# rev1.net
KiCad netlist of a schematic drawn in EAGLE
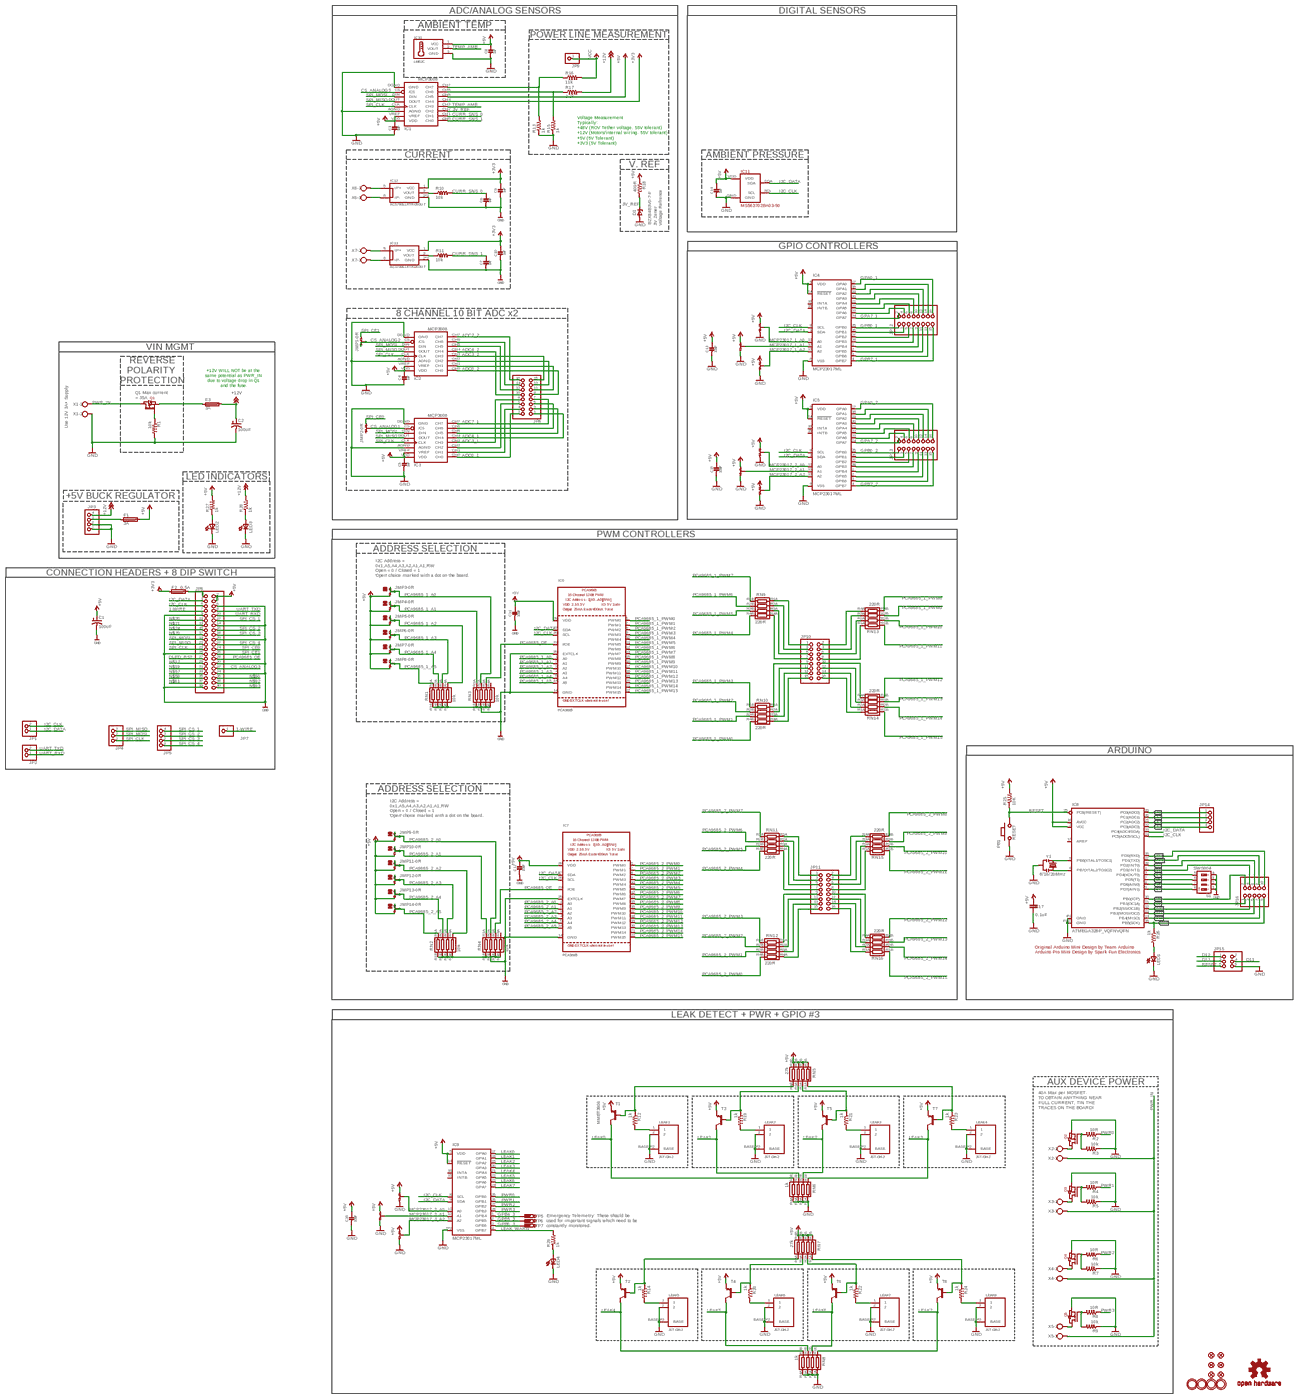
[diagram p0: schematic, sheet 1, overview]
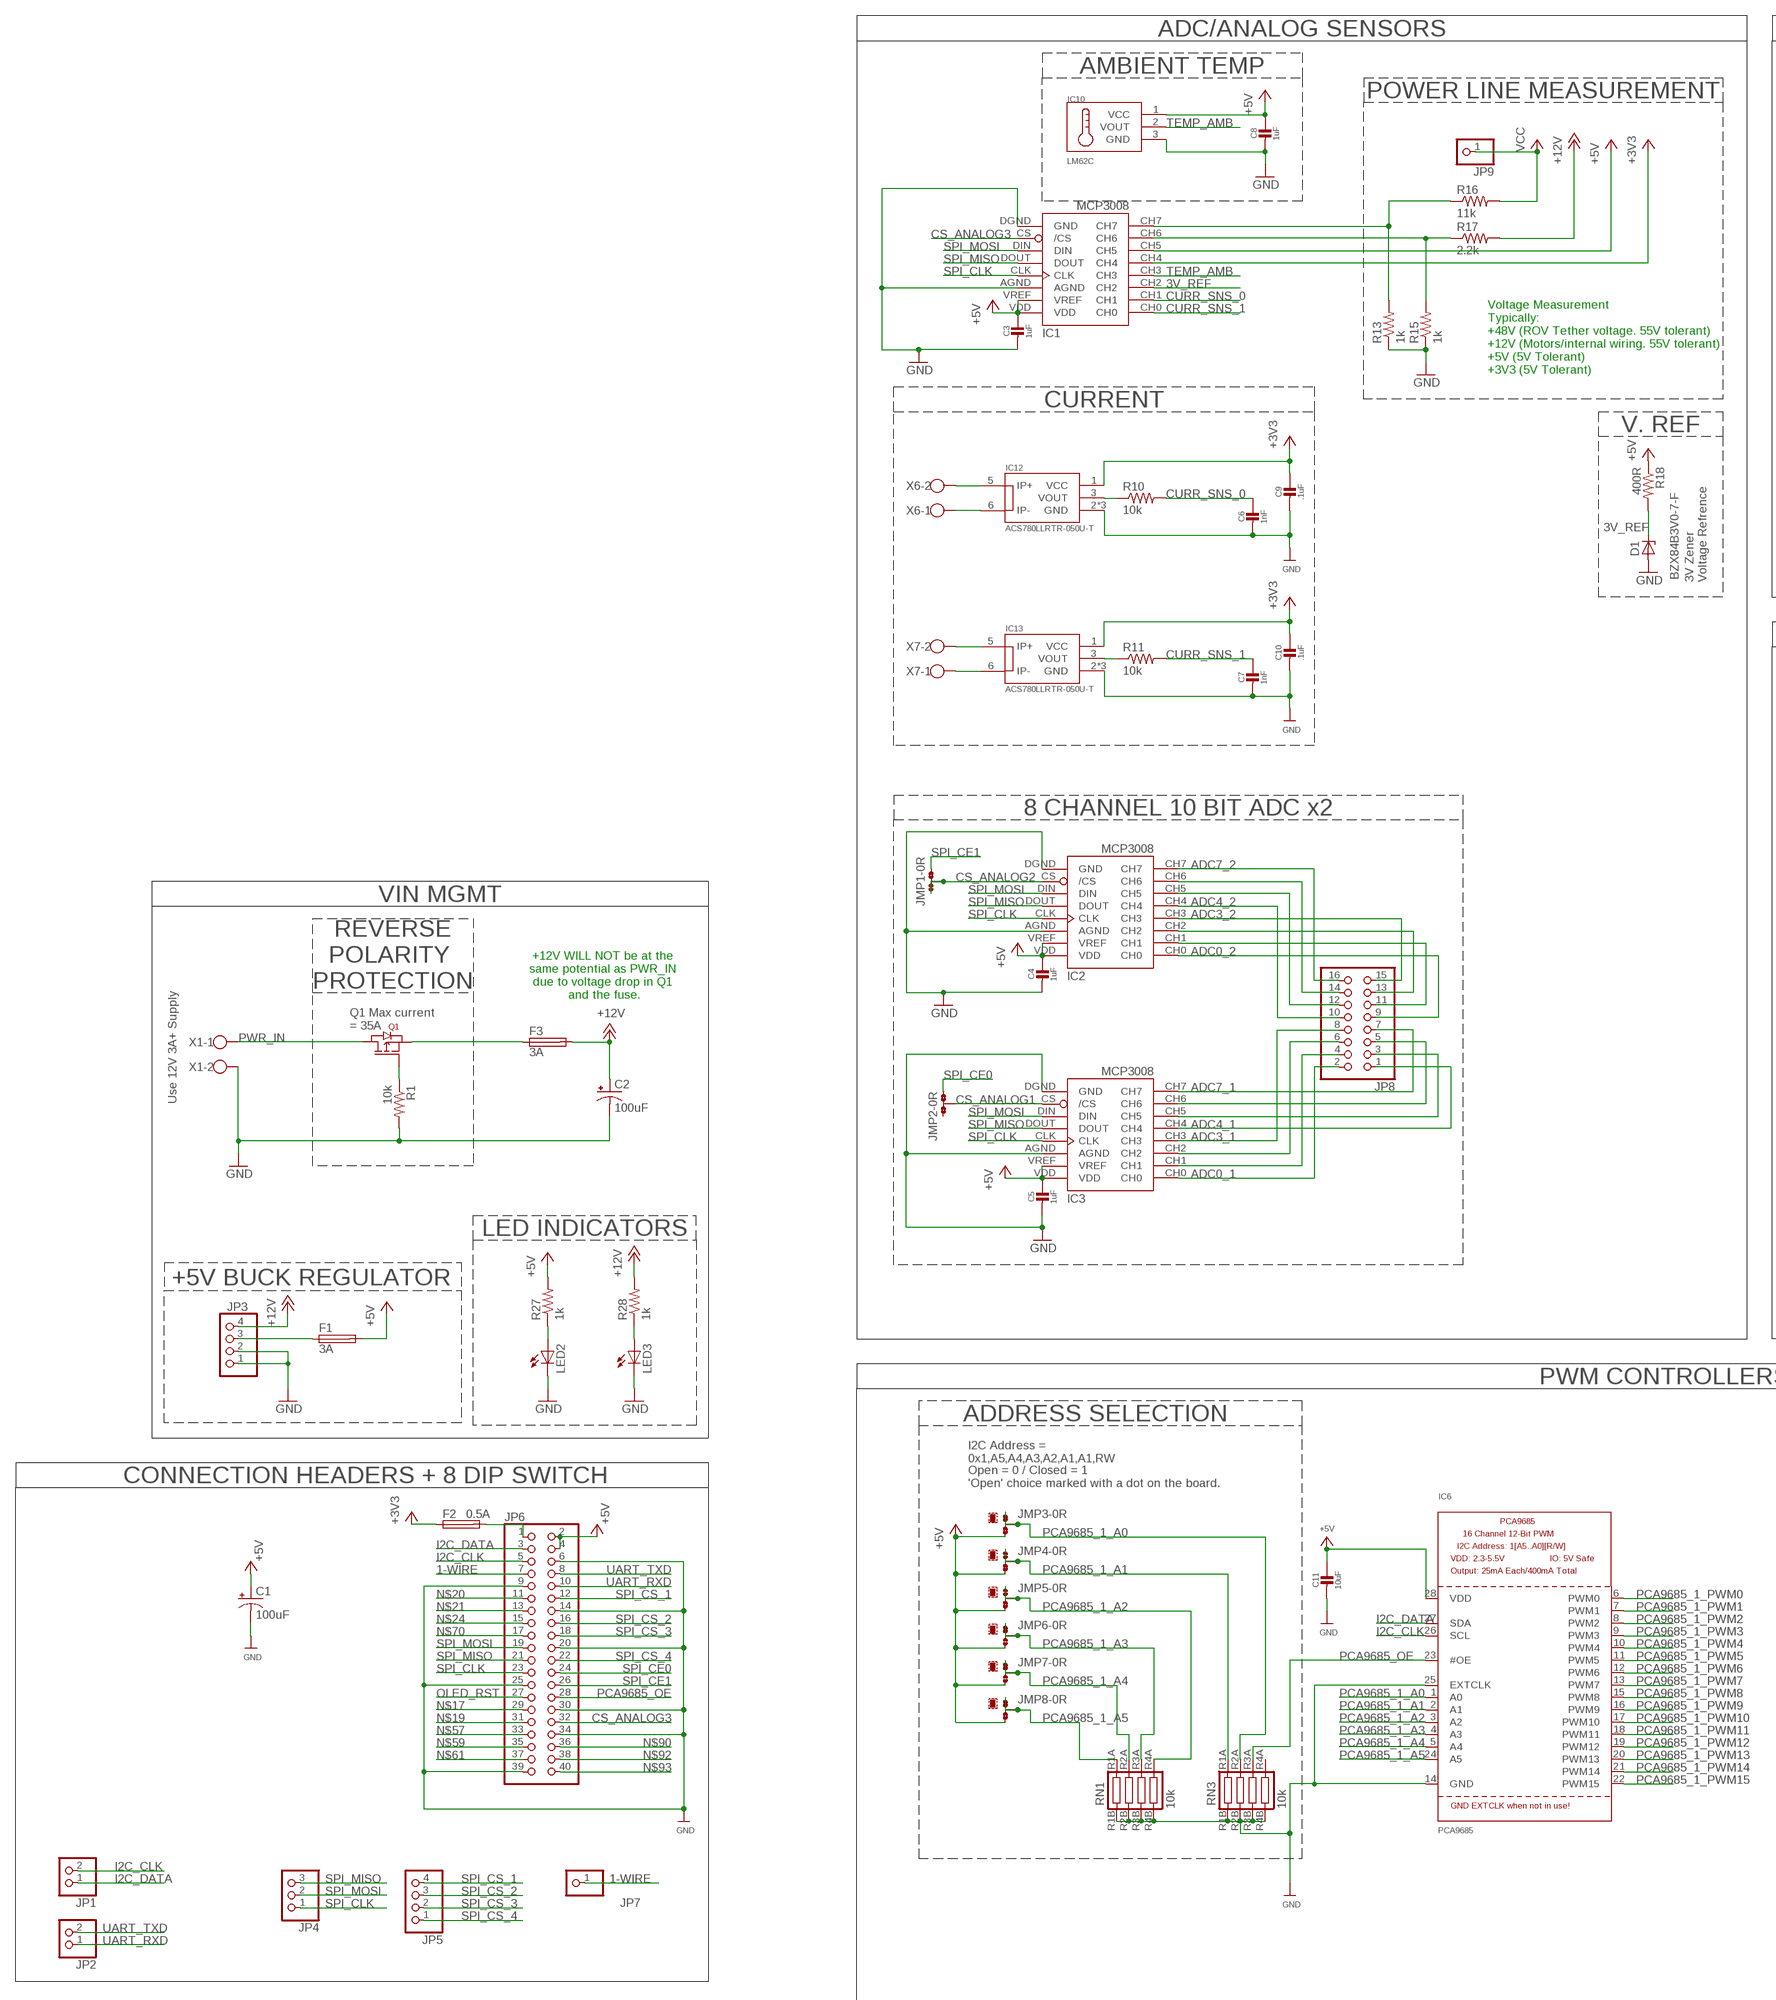
[diagram p1: schematic, sheet 1, part 1 of 4]
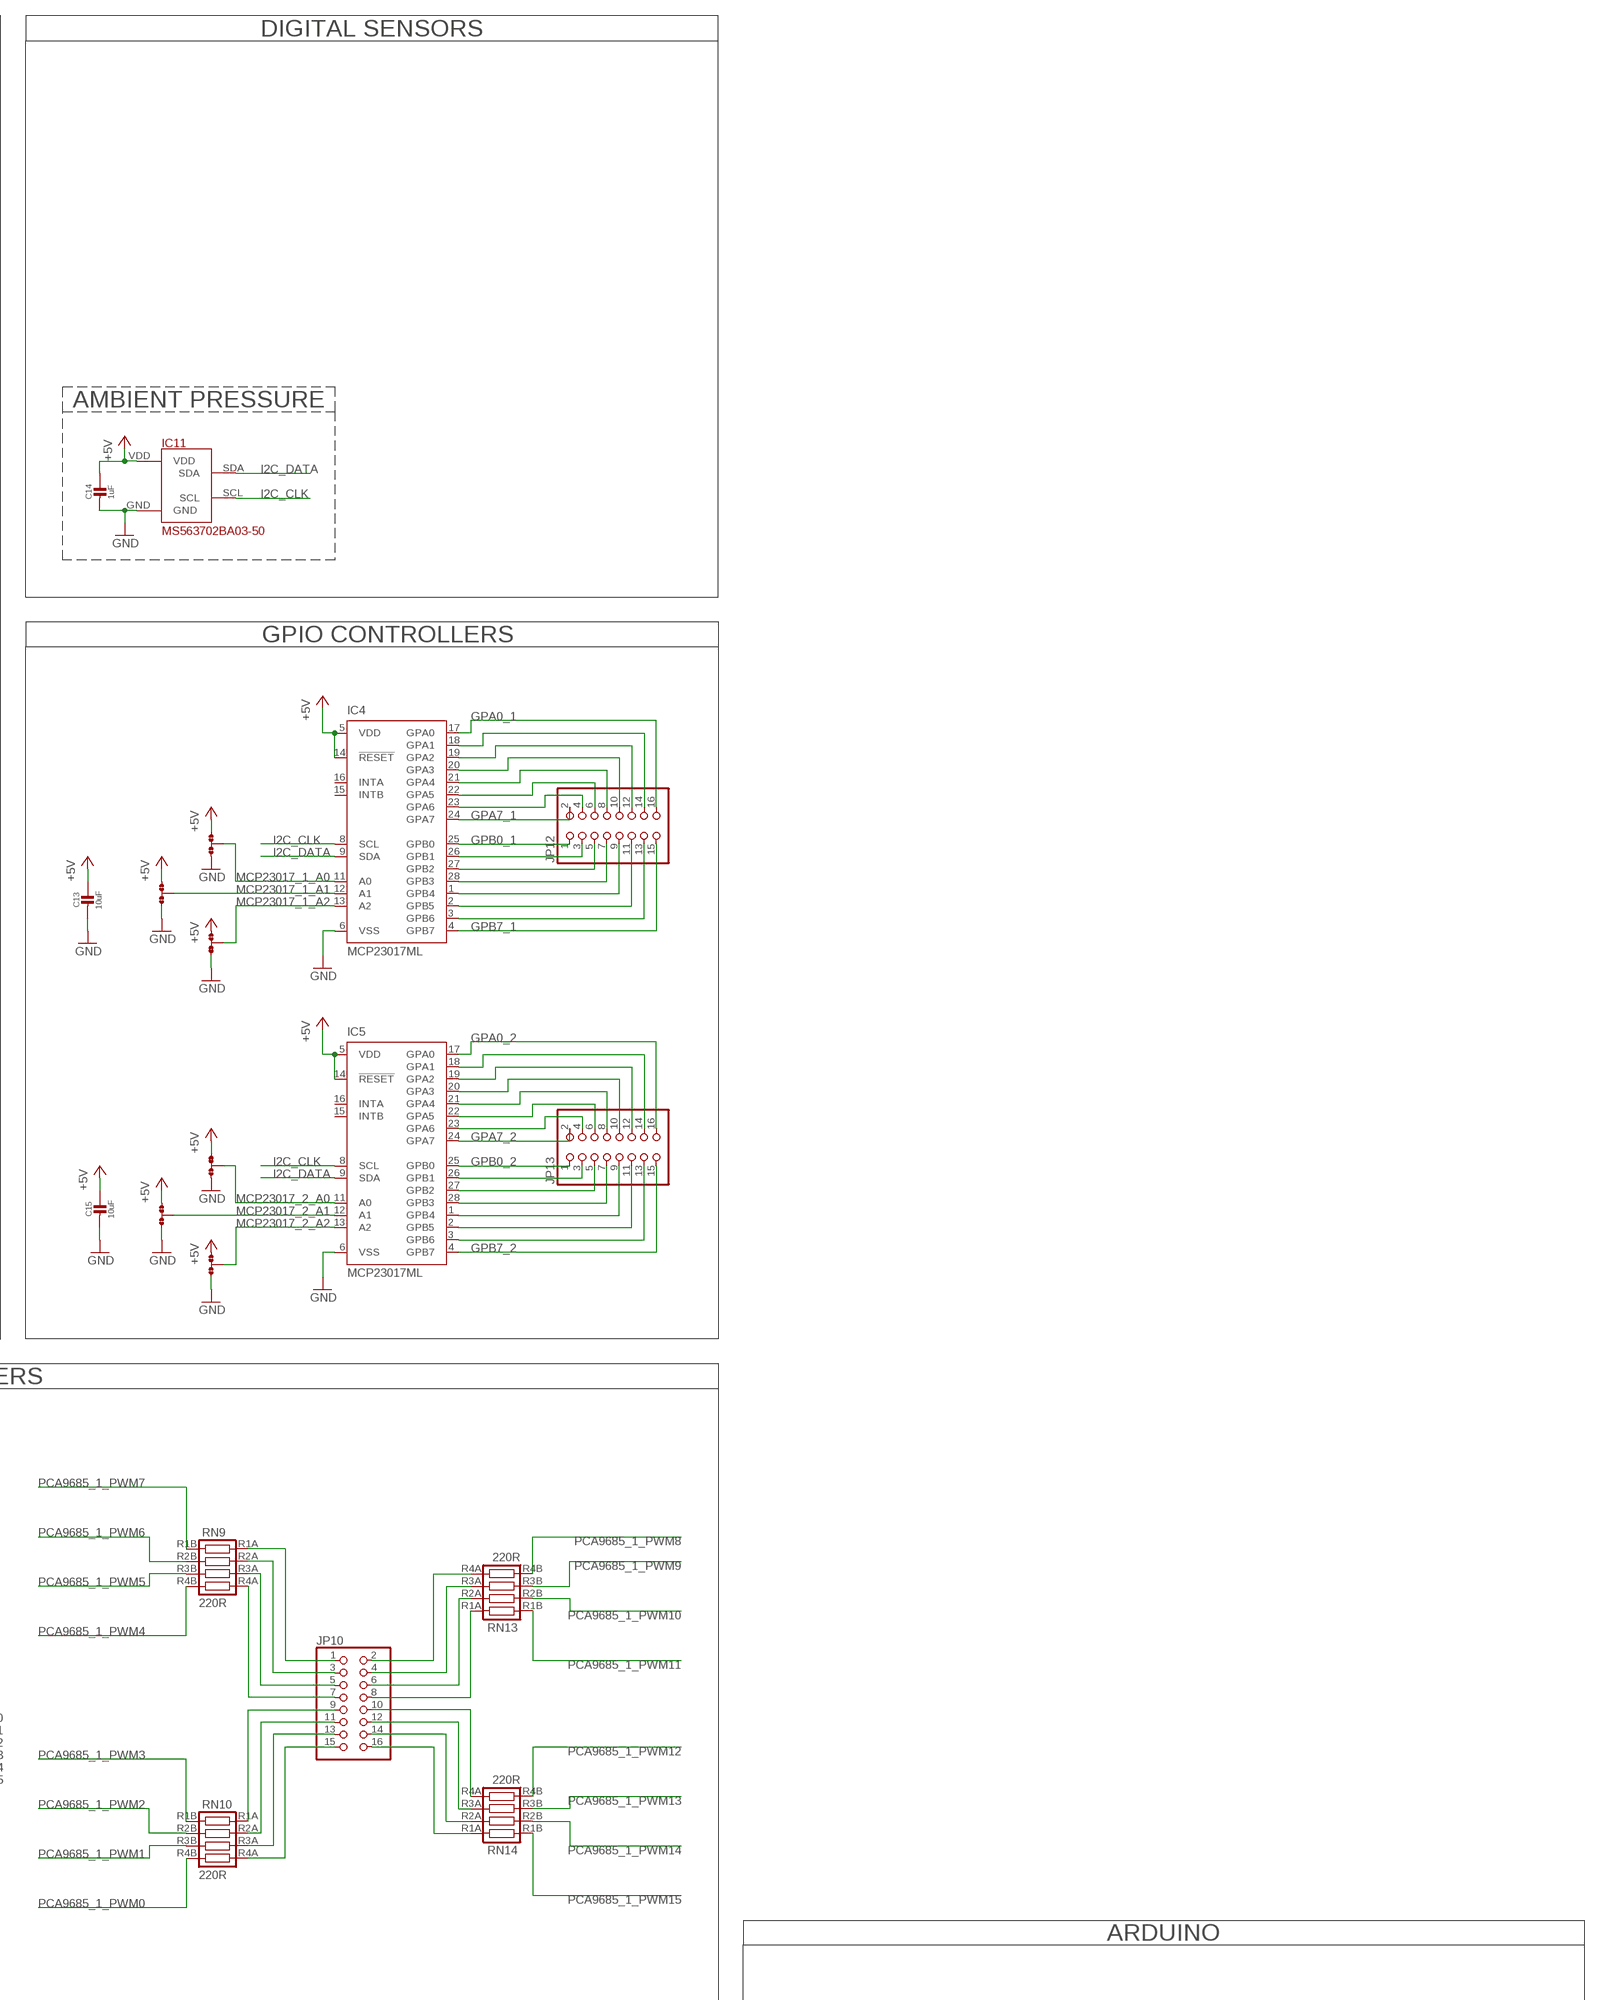
[diagram p2: schematic, sheet 1, part 2 of 4]
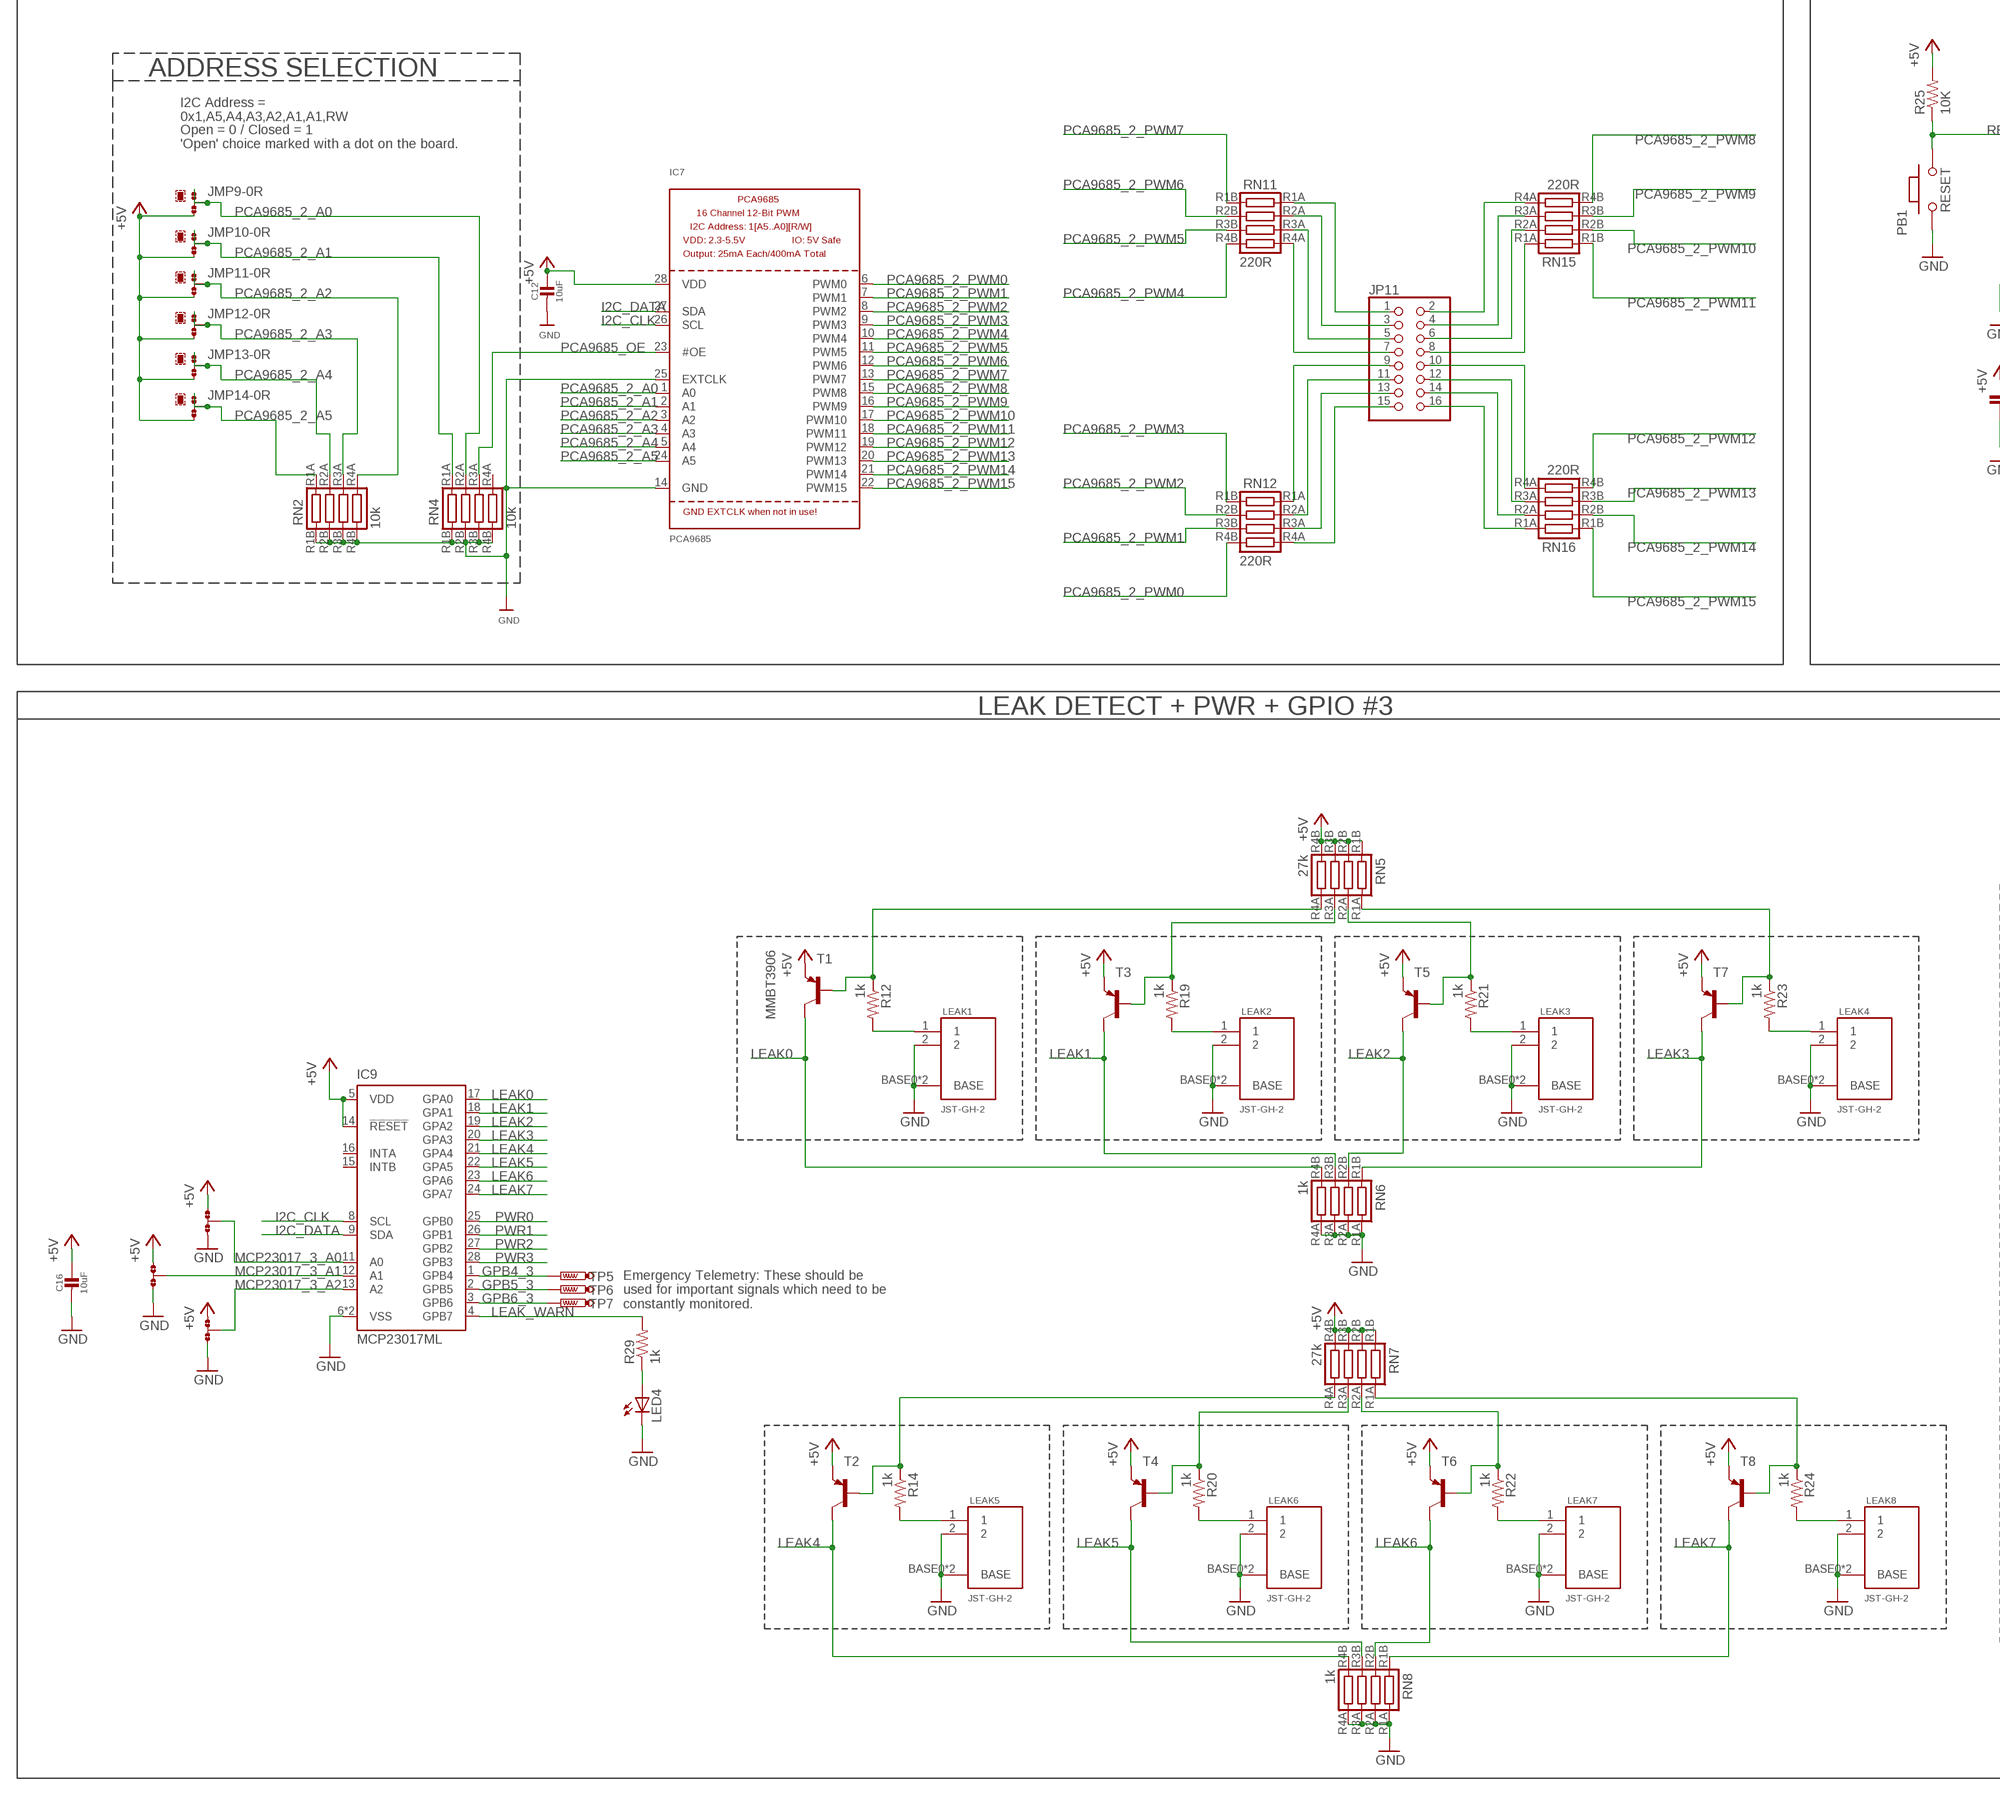
[diagram p3: schematic, sheet 1, part 3 of 4]
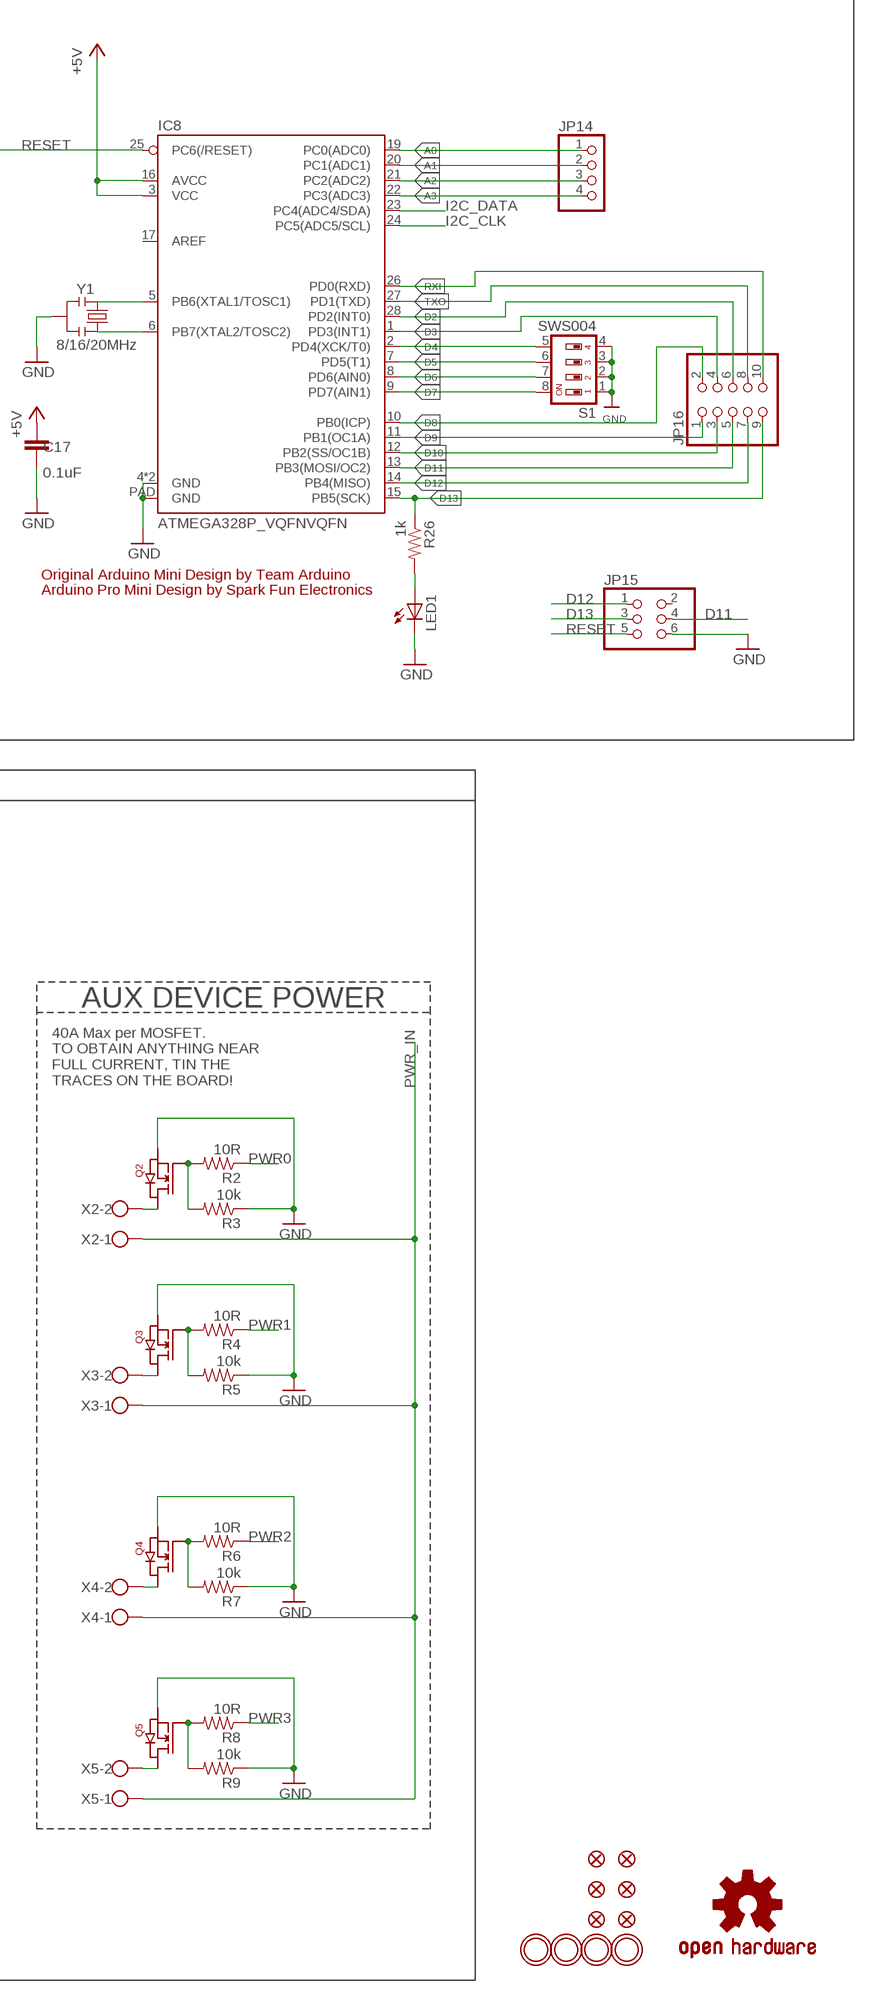
[diagram p4: schematic, sheet 1, part 4 of 4]

(export (version "E")
  (design (tool "Eeschema 10.0.6"))
  (components
    (comp (ref "1")
      (value "MOUNTINGHOLE2.5")
      (footprint "eagle-import:MOUNTINGHOLE_2.5_PLATED")
      (libsource (lib "eagle-import") (part "MOUNTINGHOLE2.5"))
    )
    (comp (ref "2")
      (value "MOUNTINGHOLE2.5")
      (footprint "eagle-import:MOUNTINGHOLE_2.5_PLATED")
      (libsource (lib "eagle-import") (part "MOUNTINGHOLE2.5"))
    )
    (comp (ref "3")
      (value "MOUNTINGHOLE2.5")
      (footprint "eagle-import:MOUNTINGHOLE_2.5_PLATED")
      (libsource (lib "eagle-import") (part "MOUNTINGHOLE2.5"))
    )
    (comp (ref "4")
      (value "MOUNTINGHOLE2.5")
      (footprint "eagle-import:MOUNTINGHOLE_2.5_PLATED")
      (libsource (lib "eagle-import") (part "MOUNTINGHOLE2.5"))
    )
    (comp (ref "5")
      (value "OSHW-LOGOS")
      (footprint "eagle-import:OSHW-LOGO-S")
      (libsource (lib "eagle-import") (part "OSHW-LOGOS"))
    )
    (comp (ref "C1")
      (value "100uF")
      (footprint "eagle-import:153CLV-0807")
      (libsource (lib "eagle-import") (part "CPOL-US153CLV-0807"))
    )
    (comp (ref "C2")
      (value "100uF")
      (footprint "eagle-import:153CLV-0807")
      (libsource (lib "eagle-import") (part "CPOL-US153CLV-0807"))
    )
    (comp (ref "C3")
      (value "1uF")
      (footprint "eagle-import:0805-NO")
      (libsource (lib "eagle-import") (part "CAP_CERAMIC0805-NOOUTLINE"))
    )
    (comp (ref "C4")
      (value "1uF")
      (footprint "eagle-import:0805-NO")
      (libsource (lib "eagle-import") (part "CAP_CERAMIC0805-NOOUTLINE"))
    )
    (comp (ref "C5")
      (value "1uF")
      (footprint "eagle-import:0805-NO")
      (libsource (lib "eagle-import") (part "CAP_CERAMIC0805-NOOUTLINE"))
    )
    (comp (ref "C6")
      (value "1nF")
      (footprint "eagle-import:0805-NO")
      (libsource (lib "eagle-import") (part "CAP_CERAMIC0805-NOOUTLINE"))
    )
    (comp (ref "C7")
      (value "1nF")
      (footprint "eagle-import:0805-NO")
      (libsource (lib "eagle-import") (part "CAP_CERAMIC0805-NOOUTLINE"))
    )
    (comp (ref "C8")
      (value "1uF")
      (footprint "eagle-import:0805-NO")
      (libsource (lib "eagle-import") (part "CAP_CERAMIC0805-NOOUTLINE"))
    )
    (comp (ref "C9")
      (value ".1uF")
      (footprint "eagle-import:0805-NO")
      (libsource (lib "eagle-import") (part "CAP_CERAMIC0805-NOOUTLINE"))
    )
    (comp (ref "C10")
      (value ".1uF")
      (footprint "eagle-import:0805-NO")
      (libsource (lib "eagle-import") (part "CAP_CERAMIC0805-NOOUTLINE"))
    )
    (comp (ref "C11")
      (value "10uF")
      (footprint "eagle-import:0805-NO")
      (libsource (lib "eagle-import") (part "CAP_CERAMIC0805-NOOUTLINE"))
    )
    (comp (ref "C12")
      (value "10uF")
      (footprint "eagle-import:0805-NO")
      (libsource (lib "eagle-import") (part "CAP_CERAMIC0805-NOOUTLINE"))
    )
    (comp (ref "C13")
      (value "10uF")
      (footprint "eagle-import:0805-NO")
      (libsource (lib "eagle-import") (part "CAP_CERAMIC0805-NOOUTLINE"))
    )
    (comp (ref "C14")
      (value "1uF")
      (footprint "eagle-import:0805-NO")
      (libsource (lib "eagle-import") (part "CAP_CERAMIC0805-NOOUTLINE"))
    )
    (comp (ref "C15")
      (value "10uF")
      (footprint "eagle-import:0805-NO")
      (libsource (lib "eagle-import") (part "CAP_CERAMIC0805-NOOUTLINE"))
    )
    (comp (ref "C16")
      (value "10uF")
      (footprint "eagle-import:0805-NO")
      (libsource (lib "eagle-import") (part "CAP_CERAMIC0805-NOOUTLINE"))
    )
    (comp (ref "C17")
      (value "0.1uF")
      (footprint "eagle-import:C0805")
      (libsource (lib "eagle-import") (part "C-EUC0805"))
    )
    (comp (ref "D1")
      (value "BZX84B3V0-7-F")
      (footprint "eagle-import:SOT23")
      (libsource (lib "eagle-import") (part "ZENER-DIODESOT23"))
    )
    (comp (ref "F1")
      (value "3A")
      (footprint "eagle-import:2920_(7351_METRIC)")
      (libsource (lib "eagle-import") (part "PTC_FUSE3"))
    )
    (comp (ref "F2")
      (value "0.5A")
      (footprint "eagle-import:1210_(3225METRIC)")
      (libsource (lib "eagle-import") (part "PTC_FUSE2"))
    )
    (comp (ref "F3")
      (value "3A")
      (footprint "eagle-import:2920_(7351_METRIC)")
      (libsource (lib "eagle-import") (part "PTC_FUSE3"))
    )
    (comp (ref "FID1")
      (value "FIDUCIAL\"\"")
      (footprint "eagle-import:FIDUCIAL_1MM")
      (libsource (lib "eagle-import") (part "FIDUCIAL{dblquote}{dblquote}"))
    )
    (comp (ref "FID2")
      (value "FIDUCIAL\"\"")
      (footprint "eagle-import:FIDUCIAL_1MM")
      (libsource (lib "eagle-import") (part "FIDUCIAL{dblquote}{dblquote}"))
    )
    (comp (ref "FID3")
      (value "FIDUCIAL\"\"")
      (footprint "eagle-import:FIDUCIAL_1MM")
      (libsource (lib "eagle-import") (part "FIDUCIAL{dblquote}{dblquote}"))
    )
    (comp (ref "FID4")
      (value "FIDUCIAL\"\"")
      (footprint "eagle-import:FIDUCIAL_1MM")
      (libsource (lib "eagle-import") (part "FIDUCIAL{dblquote}{dblquote}"))
    )
    (comp (ref "FID5")
      (value "FIDUCIAL\"\"")
      (footprint "eagle-import:FIDUCIAL_1MM")
      (libsource (lib "eagle-import") (part "FIDUCIAL{dblquote}{dblquote}"))
    )
    (comp (ref "FID6")
      (value "FIDUCIAL\"\"")
      (footprint "eagle-import:FIDUCIAL_1MM")
      (libsource (lib "eagle-import") (part "FIDUCIAL{dblquote}{dblquote}"))
    )
    (comp (ref "IC1")
      (value "U2")
      (footprint "eagle-import:MCP3008")
      (libsource (lib "eagle-import") (part "MCP3008"))
    )
    (comp (ref "IC2")
      (value "U2")
      (footprint "eagle-import:MCP3008")
      (libsource (lib "eagle-import") (part "MCP3008"))
    )
    (comp (ref "IC3")
      (value "U2")
      (footprint "eagle-import:MCP3008")
      (libsource (lib "eagle-import") (part "MCP3008"))
    )
    (comp (ref "IC4")
      (value "MCP23017ML")
      (footprint "eagle-import:QFN28-ML_6X6MM")
      (fields (field (name "MF") "MICROCHIP") (field (name "MPN") "MCP23017-E/ML"))
      (libsource (lib "eagle-import") (part "microchip_MCP23017ML"))
    )
    (comp (ref "IC5")
      (value "MCP23017ML")
      (footprint "eagle-import:QFN28-ML_6X6MM")
      (fields (field (name "MF") "MICROCHIP") (field (name "MPN") "MCP23017-E/ML"))
      (libsource (lib "eagle-import") (part "microchip_MCP23017ML"))
    )
    (comp (ref "IC6")
      (value "PCA9685")
      (footprint "eagle-import:TSSOP28")
      (libsource (lib "eagle-import") (part "PCA9685"))
    )
    (comp (ref "IC7")
      (value "PCA9685")
      (footprint "eagle-import:TSSOP28")
      (libsource (lib "eagle-import") (part "PCA9685"))
    )
    (comp (ref "IC8")
      (value "ATMEGA328P_VQFNVQFN")
      (footprint "eagle-import:VQFN-28")
      (libsource (lib "eagle-import") (part "ATMEGA328P_VQFNVQFN"))
    )
    (comp (ref "IC9")
      (value "MCP23017ML")
      (footprint "eagle-import:QFN28-ML_6X6MM")
      (fields (field (name "MF") "MICROCHIP") (field (name "MPN") "MCP23017-E/ML"))
      (libsource (lib "eagle-import") (part "MCP23017ML"))
    )
    (comp (ref "IC10")
      (value "LM62C")
      (footprint "eagle-import:SOT23-R")
      (libsource (lib "eagle-import") (part "LM62C"))
    )
    (comp (ref "IC11")
      (value "MS563702BA03-50")
      (footprint "eagle-import:MS5637")
      (libsource (lib "eagle-import") (part "PRESSURE"))
    )
    (comp (ref "IC12")
      (value "ACS780LLRTR-050U-T")
      (footprint "eagle-import:ACS781")
      (libsource (lib "eagle-import") (part "ACS781"))
    )
    (comp (ref "IC13")
      (value "ACS780LLRTR-050U-T")
      (footprint "eagle-import:ACS781")
      (libsource (lib "eagle-import") (part "ACS781"))
    )
    (comp (ref "JMP1")
      (value "0R-JUMPC")
      (footprint "eagle-import:C0R-JMP")
      (libsource (lib "eagle-import") (part "0R-JUMPC"))
    )
    (comp (ref "JMP2")
      (value "0R-JUMPC")
      (footprint "eagle-import:C0R-JMP")
      (libsource (lib "eagle-import") (part "0R-JUMPC"))
    )
    (comp (ref "JMP3")
      (value "0R-JUMPC")
      (footprint "eagle-import:C0R-JMP")
      (libsource (lib "eagle-import") (part "0R-JUMPC"))
    )
    (comp (ref "JMP4")
      (value "0R-JUMPC")
      (footprint "eagle-import:C0R-JMP")
      (libsource (lib "eagle-import") (part "0R-JUMPC"))
    )
    (comp (ref "JMP5")
      (value "0R-JUMPC")
      (footprint "eagle-import:C0R-JMP")
      (libsource (lib "eagle-import") (part "0R-JUMPC"))
    )
    (comp (ref "JMP6")
      (value "0R-JUMPC")
      (footprint "eagle-import:C0R-JMP")
      (libsource (lib "eagle-import") (part "0R-JUMPC"))
    )
    (comp (ref "JMP7")
      (value "0R-JUMPC")
      (footprint "eagle-import:C0R-JMP")
      (libsource (lib "eagle-import") (part "0R-JUMPC"))
    )
    (comp (ref "JMP8")
      (value "0R-JUMPC")
      (footprint "eagle-import:C0R-JMP")
      (libsource (lib "eagle-import") (part "0R-JUMPC"))
    )
    (comp (ref "JMP9")
      (value "0R-JUMPC")
      (footprint "eagle-import:C0R-JMP")
      (libsource (lib "eagle-import") (part "0R-JUMPC"))
    )
    (comp (ref "JMP10")
      (value "0R-JUMPC")
      (footprint "eagle-import:C0R-JMP")
      (libsource (lib "eagle-import") (part "0R-JUMPC"))
    )
    (comp (ref "JMP11")
      (value "0R-JUMPC")
      (footprint "eagle-import:C0R-JMP")
      (libsource (lib "eagle-import") (part "0R-JUMPC"))
    )
    (comp (ref "JMP12")
      (value "0R-JUMPC")
      (footprint "eagle-import:C0R-JMP")
      (libsource (lib "eagle-import") (part "0R-JUMPC"))
    )
    (comp (ref "JMP13")
      (value "0R-JUMPC")
      (footprint "eagle-import:C0R-JMP")
      (libsource (lib "eagle-import") (part "0R-JUMPC"))
    )
    (comp (ref "JMP14")
      (value "0R-JUMPC")
      (footprint "eagle-import:C0R-JMP")
      (libsource (lib "eagle-import") (part "0R-JUMPC"))
    )
    (comp (ref "JMP15")
      (value "0R-JUMPC")
      (footprint "eagle-import:C0R-JMP")
      (libsource (lib "eagle-import") (part "0R-JUMPC"))
    )
    (comp (ref "JMP16")
      (value "0R-JUMPC")
      (footprint "eagle-import:C0R-JMP")
      (libsource (lib "eagle-import") (part "0R-JUMPC"))
    )
    (comp (ref "JMP17")
      (value "0R-JUMPC")
      (footprint "eagle-import:C0R-JMP")
      (libsource (lib "eagle-import") (part "0R-JUMPC"))
    )
    (comp (ref "JMP18")
      (value "0R-JUMPC")
      (footprint "eagle-import:C0R-JMP")
      (libsource (lib "eagle-import") (part "0R-JUMPC"))
    )
    (comp (ref "JMP19")
      (value "0R-JUMPC")
      (footprint "eagle-import:C0R-JMP")
      (libsource (lib "eagle-import") (part "0R-JUMPC"))
    )
    (comp (ref "JMP20")
      (value "0R-JUMPC")
      (footprint "eagle-import:C0R-JMP")
      (libsource (lib "eagle-import") (part "0R-JUMPC"))
    )
    (comp (ref "JMP21")
      (value "0R-JUMPC")
      (footprint "eagle-import:C0R-JMP")
      (libsource (lib "eagle-import") (part "0R-JUMPC"))
    )
    (comp (ref "JMP22")
      (value "0R-JUMPC")
      (footprint "eagle-import:C0R-JMP")
      (libsource (lib "eagle-import") (part "0R-JUMPC"))
    )
    (comp (ref "JMP23")
      (value "0R-JUMPC")
      (footprint "eagle-import:C0R-JMP")
      (libsource (lib "eagle-import") (part "0R-JUMPC"))
    )
    (comp (ref "JP1")
      (value "PINHD-1X2")
      (footprint "eagle-import:1X02")
      (libsource (lib "eagle-import") (part "PINHD-1X2"))
    )
    (comp (ref "JP2")
      (value "PINHD-1X2")
      (footprint "eagle-import:1X02")
      (libsource (lib "eagle-import") (part "PINHD-1X2"))
    )
    (comp (ref "JP3")
      (value "PINHD-1X4")
      (footprint "eagle-import:1X04")
      (libsource (lib "eagle-import") (part "PINHD-1X4"))
    )
    (comp (ref "JP4")
      (value "PINHD-1X3")
      (footprint "eagle-import:1X03")
      (libsource (lib "eagle-import") (part "PINHD-1X3"))
    )
    (comp (ref "JP5")
      (value "PINHD-1X4")
      (footprint "eagle-import:1X04")
      (libsource (lib "eagle-import") (part "PINHD-1X4"))
    )
    (comp (ref "JP6")
      (value "PINHD-2X20")
      (footprint "eagle-import:2X20")
      (libsource (lib "eagle-import") (part "PINHD-2X20"))
    )
    (comp (ref "JP7")
      (value "PINHD-1X1")
      (footprint "eagle-import:1X01")
      (libsource (lib "eagle-import") (part "PINHD-1X1"))
    )
    (comp (ref "JP8")
      (value "PINHD-2X8")
      (footprint "eagle-import:2X08")
      (libsource (lib "eagle-import") (part "PINHD-2X8"))
    )
    (comp (ref "JP9")
      (value "PINHD-1X1")
      (footprint "eagle-import:1X01")
      (libsource (lib "eagle-import") (part "PINHD-1X1"))
    )
    (comp (ref "JP10")
      (value "PINHD-2X8")
      (footprint "eagle-import:2X08")
      (libsource (lib "eagle-import") (part "PINHD-2X8"))
    )
    (comp (ref "JP11")
      (value "PINHD-2X8")
      (footprint "eagle-import:2X08")
      (libsource (lib "eagle-import") (part "PINHD-2X8"))
    )
    (comp (ref "JP12")
      (value "PINHD-2X8")
      (footprint "eagle-import:2X08")
      (libsource (lib "eagle-import") (part "PINHD-2X8"))
    )
    (comp (ref "JP13")
      (value "PINHD-2X8")
      (footprint "eagle-import:2X08")
      (libsource (lib "eagle-import") (part "PINHD-2X8"))
    )
    (comp (ref "JP14")
      (value "PINHD-1X4")
      (footprint "eagle-import:1X04")
      (libsource (lib "eagle-import") (part "PINHD-1X4"))
    )
    (comp (ref "JP15")
      (value "PINHD-2X3")
      (footprint "eagle-import:2X03")
      (libsource (lib "eagle-import") (part "PINHD-2X3"))
    )
    (comp (ref "JP16")
      (value "PINHD-2X5")
      (footprint "eagle-import:2X05")
      (libsource (lib "eagle-import") (part "PINHD-2X5"))
    )
    (comp (ref "LEAK1")
      (value "JST-GH-2")
      (footprint "eagle-import:JST-GH")
      (libsource (lib "eagle-import") (part "JST-GH-2"))
    )
    (comp (ref "LEAK2")
      (value "JST-GH-2")
      (footprint "eagle-import:JST-GH")
      (libsource (lib "eagle-import") (part "JST-GH-2"))
    )
    (comp (ref "LEAK3")
      (value "JST-GH-2")
      (footprint "eagle-import:JST-GH")
      (libsource (lib "eagle-import") (part "JST-GH-2"))
    )
    (comp (ref "LEAK4")
      (value "JST-GH-2")
      (footprint "eagle-import:JST-GH")
      (libsource (lib "eagle-import") (part "JST-GH-2"))
    )
    (comp (ref "LEAK5")
      (value "JST-GH-2")
      (footprint "eagle-import:JST-GH")
      (libsource (lib "eagle-import") (part "JST-GH-2"))
    )
    (comp (ref "LEAK6")
      (value "JST-GH-2")
      (footprint "eagle-import:JST-GH")
      (libsource (lib "eagle-import") (part "JST-GH-2"))
    )
    (comp (ref "LEAK7")
      (value "JST-GH-2")
      (footprint "eagle-import:JST-GH")
      (libsource (lib "eagle-import") (part "JST-GH-2"))
    )
    (comp (ref "LEAK8")
      (value "JST-GH-2")
      (footprint "eagle-import:JST-GH")
      (libsource (lib "eagle-import") (part "JST-GH-2"))
    )
    (comp (ref "LED1")
      (value "LED_E")
      (footprint "eagle-import:LED_1206")
      (libsource (lib "eagle-import") (part "LED_E"))
    )
    (comp (ref "LED2")
      (value "LED_E")
      (footprint "eagle-import:LED_1206")
      (libsource (lib "eagle-import") (part "LED_E"))
    )
    (comp (ref "LED3")
      (value "LED_E")
      (footprint "eagle-import:LED_1206")
      (libsource (lib "eagle-import") (part "LED_E"))
    )
    (comp (ref "LED4")
      (value "LED_E")
      (footprint "eagle-import:LED_1206")
      (libsource (lib "eagle-import") (part "LED_E"))
    )
    (comp (ref "PB1")
      (value "RESET")
      (footprint "eagle-import:SMD_157SW")
      (fields (field (name "PART_NUMBER") "IT-1185AP1C-160G-G_T&R"))
      (libsource (lib "eagle-import") (part "0173_IT-1185AP1C-160G-G_T&R"))
    )
    (comp (ref "Q1")
      (value "1212_PFET")
      (footprint "eagle-import:POWERPACK_1212-8")
      (libsource (lib "eagle-import") (part "1212_PFET"))
    )
    (comp (ref "Q2")
      (value "1212_NFET")
      (footprint "eagle-import:POWERPACK_1212-8")
      (libsource (lib "eagle-import") (part "1212_NFET"))
    )
    (comp (ref "Q3")
      (value "1212_NFET")
      (footprint "eagle-import:POWERPACK_1212-8")
      (libsource (lib "eagle-import") (part "1212_NFET"))
    )
    (comp (ref "Q4")
      (value "1212_NFET")
      (footprint "eagle-import:POWERPACK_1212-8")
      (libsource (lib "eagle-import") (part "1212_NFET"))
    )
    (comp (ref "Q5")
      (value "1212_NFET")
      (footprint "eagle-import:POWERPACK_1212-8")
      (libsource (lib "eagle-import") (part "1212_NFET"))
    )
    (comp (ref "R1")
      (value "10k")
      (footprint "eagle-import:R0402")
      (libsource (lib "eagle-import") (part "R-US_R0402"))
    )
    (comp (ref "R2")
      (value "10R")
      (footprint "eagle-import:R0805")
      (libsource (lib "eagle-import") (part "resistor_R-US_R0805"))
    )
    (comp (ref "R3")
      (value "10k")
      (footprint "eagle-import:R0805")
      (libsource (lib "eagle-import") (part "resistor_R-US_R0805"))
    )
    (comp (ref "R4")
      (value "10R")
      (footprint "eagle-import:R0805")
      (libsource (lib "eagle-import") (part "resistor_R-US_R0805"))
    )
    (comp (ref "R5")
      (value "10k")
      (footprint "eagle-import:R0805")
      (libsource (lib "eagle-import") (part "resistor_R-US_R0805"))
    )
    (comp (ref "R6")
      (value "10R")
      (footprint "eagle-import:R0805")
      (libsource (lib "eagle-import") (part "resistor_R-US_R0805"))
    )
    (comp (ref "R7")
      (value "10k")
      (footprint "eagle-import:R0805")
      (libsource (lib "eagle-import") (part "resistor_R-US_R0805"))
    )
    (comp (ref "R8")
      (value "10R")
      (footprint "eagle-import:R0805")
      (libsource (lib "eagle-import") (part "resistor_R-US_R0805"))
    )
    (comp (ref "R9")
      (value "10k")
      (footprint "eagle-import:R0805")
      (libsource (lib "eagle-import") (part "resistor_R-US_R0805"))
    )
    (comp (ref "R10")
      (value "10k")
      (footprint "eagle-import:R0402")
      (libsource (lib "eagle-import") (part "R-US_R0402"))
    )
    (comp (ref "R11")
      (value "10k")
      (footprint "eagle-import:R0402")
      (libsource (lib "eagle-import") (part "R-US_R0402"))
    )
    (comp (ref "R12")
      (value "1k")
      (footprint "eagle-import:R0402")
      (libsource (lib "eagle-import") (part "R-US_R0402"))
    )
    (comp (ref "R13")
      (value "1k")
      (footprint "eagle-import:R0402")
      (libsource (lib "eagle-import") (part "R-US_R0402"))
    )
    (comp (ref "R14")
      (value "1k")
      (footprint "eagle-import:R0402")
      (libsource (lib "eagle-import") (part "R-US_R0402"))
    )
    (comp (ref "R15")
      (value "1k")
      (footprint "eagle-import:R0402")
      (libsource (lib "eagle-import") (part "R-US_R0402"))
    )
    (comp (ref "R16")
      (value "11k")
      (footprint "eagle-import:R0402")
      (libsource (lib "eagle-import") (part "R-US_R0402"))
    )
    (comp (ref "R17")
      (value "2.2k")
      (footprint "eagle-import:R0402")
      (libsource (lib "eagle-import") (part "R-US_R0402"))
    )
    (comp (ref "R18")
      (value "400R")
      (footprint "eagle-import:R0402")
      (libsource (lib "eagle-import") (part "R-US_R0402"))
    )
    (comp (ref "R19")
      (value "1k")
      (footprint "eagle-import:R0402")
      (libsource (lib "eagle-import") (part "R-US_R0402"))
    )
    (comp (ref "R20")
      (value "1k")
      (footprint "eagle-import:R0402")
      (libsource (lib "eagle-import") (part "R-US_R0402"))
    )
    (comp (ref "R21")
      (value "1k")
      (footprint "eagle-import:R0402")
      (libsource (lib "eagle-import") (part "R-US_R0402"))
    )
    (comp (ref "R22")
      (value "1k")
      (footprint "eagle-import:R0402")
      (libsource (lib "eagle-import") (part "R-US_R0402"))
    )
    (comp (ref "R23")
      (value "1k")
      (footprint "eagle-import:R0402")
      (libsource (lib "eagle-import") (part "R-US_R0402"))
    )
    (comp (ref "R24")
      (value "1k")
      (footprint "eagle-import:R0402")
      (libsource (lib "eagle-import") (part "R-US_R0402"))
    )
    (comp (ref "R25")
      (value "10K")
      (footprint "eagle-import:R0805")
      (libsource (lib "eagle-import") (part "R-US_R0805"))
    )
    (comp (ref "R26")
      (value "1k")
      (footprint "eagle-import:R0805")
      (libsource (lib "eagle-import") (part "R-US_R0805"))
    )
    (comp (ref "R27")
      (value "1k")
      (footprint "eagle-import:R0805")
      (libsource (lib "eagle-import") (part "resistor_R-US_R0805"))
    )
    (comp (ref "R28")
      (value "1k")
      (footprint "eagle-import:R0805")
      (libsource (lib "eagle-import") (part "resistor_R-US_R0805"))
    )
    (comp (ref "R29")
      (value "1k")
      (footprint "eagle-import:R0805")
      (libsource (lib "eagle-import") (part "resistor_R-US_R0805"))
    )
    (comp (ref "RN1")
      (value "10k")
      (footprint "eagle-import:0804_RN")
      (libsource (lib "eagle-import") (part "RN4_0804"))
    )
    (comp (ref "RN2")
      (value "10k")
      (footprint "eagle-import:0804_RN")
      (libsource (lib "eagle-import") (part "RN4_0804"))
    )
    (comp (ref "RN3")
      (value "10k")
      (footprint "eagle-import:0804_RN")
      (libsource (lib "eagle-import") (part "RN4_0804"))
    )
    (comp (ref "RN4")
      (value "10k")
      (footprint "eagle-import:0804_RN")
      (libsource (lib "eagle-import") (part "RN4_0804"))
    )
    (comp (ref "RN5")
      (value "27k")
      (footprint "eagle-import:0804_RN")
      (libsource (lib "eagle-import") (part "RN4_0804"))
    )
    (comp (ref "RN6")
      (value "1k")
      (footprint "eagle-import:0804_RN")
      (libsource (lib "eagle-import") (part "RN4_0804"))
    )
    (comp (ref "RN7")
      (value "27k")
      (footprint "eagle-import:0804_RN")
      (libsource (lib "eagle-import") (part "RN4_0804"))
    )
    (comp (ref "RN8")
      (value "1k")
      (footprint "eagle-import:0804_RN")
      (libsource (lib "eagle-import") (part "RN4_0804"))
    )
    (comp (ref "RN9")
      (value "220R")
      (footprint "eagle-import:0804_RN")
      (libsource (lib "eagle-import") (part "RN4_0804"))
    )
    (comp (ref "RN10")
      (value "220R")
      (footprint "eagle-import:0804_RN")
      (libsource (lib "eagle-import") (part "RN4_0804"))
    )
    (comp (ref "RN11")
      (value "220R")
      (footprint "eagle-import:0804_RN")
      (libsource (lib "eagle-import") (part "RN4_0804"))
    )
    (comp (ref "RN12")
      (value "220R")
      (footprint "eagle-import:0804_RN")
      (libsource (lib "eagle-import") (part "RN4_0804"))
    )
    (comp (ref "RN13")
      (value "220R")
      (footprint "eagle-import:0804_RN")
      (libsource (lib "eagle-import") (part "RN4_0804"))
    )
    (comp (ref "RN14")
      (value "220R")
      (footprint "eagle-import:0804_RN")
      (libsource (lib "eagle-import") (part "RN4_0804"))
    )
    (comp (ref "RN15")
      (value "220R")
      (footprint "eagle-import:0804_RN")
      (libsource (lib "eagle-import") (part "RN4_0804"))
    )
    (comp (ref "RN16")
      (value "220R")
      (footprint "eagle-import:0804_RN")
      (libsource (lib "eagle-import") (part "RN4_0804"))
    )
    (comp (ref "S1")
      (value "SWS004")
      (footprint "eagle-import:SMS-004")
      (libsource (lib "eagle-import") (part "SWS004"))
    )
    (comp (ref "T1")
      (value "MMBT3906")
      (footprint "eagle-import:SOT23-BEC")
      (libsource (lib "eagle-import") (part "-PNP-SOT23-BECBC807-40"))
    )
    (comp (ref "T2")
      (value "BC807-40-PNP-SOT23-BEC")
      (footprint "eagle-import:SOT23-BEC")
      (libsource (lib "eagle-import") (part "-PNP-SOT23-BECBC807-40"))
    )
    (comp (ref "T3")
      (value "BC807-40-PNP-SOT23-BEC")
      (footprint "eagle-import:SOT23-BEC")
      (libsource (lib "eagle-import") (part "-PNP-SOT23-BECBC807-40"))
    )
    (comp (ref "T4")
      (value "BC807-40-PNP-SOT23-BEC")
      (footprint "eagle-import:SOT23-BEC")
      (libsource (lib "eagle-import") (part "-PNP-SOT23-BECBC807-40"))
    )
    (comp (ref "T5")
      (value "BC807-40-PNP-SOT23-BEC")
      (footprint "eagle-import:SOT23-BEC")
      (libsource (lib "eagle-import") (part "-PNP-SOT23-BECBC807-40"))
    )
    (comp (ref "T6")
      (value "BC807-40-PNP-SOT23-BEC")
      (footprint "eagle-import:SOT23-BEC")
      (libsource (lib "eagle-import") (part "-PNP-SOT23-BECBC807-40"))
    )
    (comp (ref "T7")
      (value "BC807-40-PNP-SOT23-BEC")
      (footprint "eagle-import:SOT23-BEC")
      (libsource (lib "eagle-import") (part "-PNP-SOT23-BECBC807-40"))
    )
    (comp (ref "T8")
      (value "BC807-40-PNP-SOT23-BEC")
      (footprint "eagle-import:SOT23-BEC")
      (libsource (lib "eagle-import") (part "-PNP-SOT23-BECBC807-40"))
    )
    (comp (ref "TP5")
      (value "PTR1TP06R")
      (footprint "eagle-import:TP06R")
      (libsource (lib "eagle-import") (part "PTR1TP06R"))
    )
    (comp (ref "TP6")
      (value "PTR1TP06R")
      (footprint "eagle-import:TP06R")
      (libsource (lib "eagle-import") (part "PTR1TP06R"))
    )
    (comp (ref "TP7")
      (value "PTR1TP06R")
      (footprint "eagle-import:TP06R")
      (libsource (lib "eagle-import") (part "PTR1TP06R"))
    )
    (comp (ref "X1")
      (value "W237-102")
      (footprint "eagle-import:W237-102")
      (fields (field (name "MPN") "237-102"))
      (libsource (lib "eagle-import") (part "W237-102"))
    )
    (comp (ref "X2")
      (value "W237-102")
      (footprint "eagle-import:W237-102")
      (fields (field (name "MPN") "237-102"))
      (libsource (lib "eagle-import") (part "W237-102"))
    )
    (comp (ref "X3")
      (value "W237-102")
      (footprint "eagle-import:W237-102")
      (fields (field (name "MPN") "237-102"))
      (libsource (lib "eagle-import") (part "W237-102"))
    )
    (comp (ref "X4")
      (value "W237-102")
      (footprint "eagle-import:W237-102")
      (fields (field (name "MPN") "237-102"))
      (libsource (lib "eagle-import") (part "W237-102"))
    )
    (comp (ref "X5")
      (value "W237-102")
      (footprint "eagle-import:W237-102")
      (fields (field (name "MPN") "237-102"))
      (libsource (lib "eagle-import") (part "W237-102"))
    )
    (comp (ref "X6")
      (value "W237-102")
      (footprint "eagle-import:W237-102")
      (fields (field (name "MPN") "237-102"))
      (libsource (lib "eagle-import") (part "W237-102"))
    )
    (comp (ref "X7")
      (value "W237-102")
      (footprint "eagle-import:W237-102")
      (fields (field (name "MPN") "237-102"))
      (libsource (lib "eagle-import") (part "W237-102"))
    )
    (comp (ref "Y1")
      (value "8/16/20MHz")
      (footprint "eagle-import:RESONATOR-SMD-1_1")
      (libsource (lib "eagle-import") (part "RESONATOR1{colon}1"))
    )
  )
  (nets
    (net (code "1") (name "+3V3") (class "Default")
      (node (ref "C10") (pin "1") (pinfunction "1_1") (pintype "passive"))
      (node (ref "C9") (pin "1") (pinfunction "1_1") (pintype "passive"))
      (node (ref "F2") (pin "1") (pinfunction "1_1") (pintype "passive"))
      (node (ref "IC1") (pin "CH4") (pinfunction "CH4_CH4") (pintype "input"))
      (node (ref "IC12") (pin "1") (pinfunction "VCC_1") (pintype "bidirectional"))
      (node (ref "IC13") (pin "1") (pinfunction "VCC_1") (pintype "bidirectional"))
    )
    (net (code "2") (name "+5V") (class "Default")
      (node (ref "C1") (pin "+") (pinfunction "+_+") (pintype "passive"))
      (node (ref "C11") (pin "1") (pinfunction "1_1") (pintype "passive"))
      (node (ref "C12") (pin "1") (pinfunction "1_1") (pintype "passive"))
      (node (ref "C13") (pin "1") (pinfunction "1_1") (pintype "passive"))
      (node (ref "C14") (pin "1") (pinfunction "1_1") (pintype "passive"))
      (node (ref "C15") (pin "1") (pinfunction "1_1") (pintype "passive"))
      (node (ref "C16") (pin "1") (pinfunction "1_1") (pintype "passive"))
      (node (ref "C17") (pin "2") (pinfunction "2_2") (pintype "passive"))
      (node (ref "C3") (pin "1") (pinfunction "1_1") (pintype "passive"))
      (node (ref "C4") (pin "1") (pinfunction "1_1") (pintype "passive"))
      (node (ref "C5") (pin "1") (pinfunction "1_1") (pintype "passive"))
      (node (ref "C8") (pin "1") (pinfunction "1_1") (pintype "passive"))
      (node (ref "F1") (pin "2") (pinfunction "2_2") (pintype "passive"))
      (node (ref "IC1") (pin "CH5") (pinfunction "CH5_CH5") (pintype "input"))
      (node (ref "IC1") (pin "VDD") (pinfunction "VDD_VDD") (pintype "power_in"))
      (node (ref "IC1") (pin "VREF") (pinfunction "VREF_VREF") (pintype "input"))
      (node (ref "IC10") (pin "1") (pinfunction "VCC_1") (pintype "bidirectional"))
      (node (ref "IC11") (pin "VDD") (pinfunction "VDD_VDD") (pintype "bidirectional"))
      (node (ref "IC2") (pin "VDD") (pinfunction "VDD_VDD") (pintype "power_in"))
      (node (ref "IC2") (pin "VREF") (pinfunction "VREF_VREF") (pintype "input"))
      (node (ref "IC3") (pin "VDD") (pinfunction "VDD_VDD") (pintype "power_in"))
      (node (ref "IC3") (pin "VREF") (pinfunction "VREF_VREF") (pintype "input"))
      (node (ref "IC4") (pin "14") (pinfunction "~{RESET}_14") (pintype "input"))
      (node (ref "IC4") (pin "5") (pinfunction "VDD_5") (pintype "power_in"))
      (node (ref "IC5") (pin "14") (pinfunction "~{RESET}_14") (pintype "input"))
      (node (ref "IC5") (pin "5") (pinfunction "VDD_5") (pintype "power_in"))
      (node (ref "IC6") (pin "28") (pinfunction "VDD_28") (pintype "power_in"))
      (node (ref "IC7") (pin "28") (pinfunction "VDD_28") (pintype "power_in"))
      (node (ref "IC8") (pin "16") (pinfunction "AVCC_16") (pintype "bidirectional"))
      (node (ref "IC8") (pin "3") (pinfunction "VCC_3") (pintype "bidirectional"))
      (node (ref "IC9") (pin "14") (pinfunction "~{RESET}_14") (pintype "input"))
      (node (ref "IC9") (pin "5") (pinfunction "VDD_5") (pintype "power_in"))
      (node (ref "JMP10") (pin "3") (pinfunction "3_3") (pintype "passive"))
      (node (ref "JMP11") (pin "3") (pinfunction "3_3") (pintype "passive"))
      (node (ref "JMP12") (pin "3") (pinfunction "3_3") (pintype "passive"))
      (node (ref "JMP13") (pin "3") (pinfunction "3_3") (pintype "passive"))
      (node (ref "JMP14") (pin "3") (pinfunction "3_3") (pintype "passive"))
      (node (ref "JMP15") (pin "1") (pinfunction "1_1") (pintype "passive"))
      (node (ref "JMP16") (pin "1") (pinfunction "1_1") (pintype "passive"))
      (node (ref "JMP17") (pin "1") (pinfunction "1_1") (pintype "passive"))
      (node (ref "JMP18") (pin "1") (pinfunction "1_1") (pintype "passive"))
      (node (ref "JMP19") (pin "1") (pinfunction "1_1") (pintype "passive"))
      (node (ref "JMP20") (pin "1") (pinfunction "1_1") (pintype "passive"))
      (node (ref "JMP21") (pin "1") (pinfunction "1_1") (pintype "passive"))
      (node (ref "JMP22") (pin "1") (pinfunction "1_1") (pintype "passive"))
      (node (ref "JMP23") (pin "1") (pinfunction "1_1") (pintype "passive"))
      (node (ref "JMP3") (pin "3") (pinfunction "3_3") (pintype "passive"))
      (node (ref "JMP4") (pin "3") (pinfunction "3_3") (pintype "passive"))
      (node (ref "JMP5") (pin "3") (pinfunction "3_3") (pintype "passive"))
      (node (ref "JMP6") (pin "3") (pinfunction "3_3") (pintype "passive"))
      (node (ref "JMP7") (pin "3") (pinfunction "3_3") (pintype "passive"))
      (node (ref "JMP8") (pin "3") (pinfunction "3_3") (pintype "passive"))
      (node (ref "JMP9") (pin "3") (pinfunction "3_3") (pintype "passive"))
      (node (ref "JP6") (pin "2") (pinfunction "2_2") (pintype "passive"))
      (node (ref "JP6") (pin "4") (pinfunction "4_4") (pintype "passive"))
      (node (ref "R18") (pin "1") (pinfunction "1_1") (pintype "passive"))
      (node (ref "R25") (pin "2") (pinfunction "2_2") (pintype "passive"))
      (node (ref "R27") (pin "2") (pinfunction "2_2") (pintype "passive"))
      (node (ref "RN5") (pin "R1B") (pinfunction "1_R1B") (pintype "passive"))
      (node (ref "RN5") (pin "R2B") (pinfunction "2_R2B") (pintype "passive"))
      (node (ref "RN5") (pin "R3B") (pinfunction "3_R3B") (pintype "passive"))
      (node (ref "RN5") (pin "R4B") (pinfunction "4_R4B") (pintype "passive"))
      (node (ref "RN7") (pin "R1B") (pinfunction "1_R1B") (pintype "passive"))
      (node (ref "RN7") (pin "R2B") (pinfunction "2_R2B") (pintype "passive"))
      (node (ref "RN7") (pin "R3B") (pinfunction "3_R3B") (pintype "passive"))
      (node (ref "RN7") (pin "R4B") (pinfunction "4_R4B") (pintype "passive"))
      (node (ref "T1") (pin "E") (pinfunction "E_E") (pintype "passive"))
      (node (ref "T2") (pin "E") (pinfunction "E_E") (pintype "passive"))
      (node (ref "T3") (pin "E") (pinfunction "E_E") (pintype "passive"))
      (node (ref "T4") (pin "E") (pinfunction "E_E") (pintype "passive"))
      (node (ref "T5") (pin "E") (pinfunction "E_E") (pintype "passive"))
      (node (ref "T6") (pin "E") (pinfunction "E_E") (pintype "passive"))
      (node (ref "T7") (pin "E") (pinfunction "E_E") (pintype "passive"))
      (node (ref "T8") (pin "E") (pinfunction "E_E") (pintype "passive"))
    )
    (net (code "3") (name "+12V") (class "Default")
      (node (ref "C2") (pin "+") (pinfunction "+_+") (pintype "passive"))
      (node (ref "F3") (pin "2") (pinfunction "2_2") (pintype "passive"))
      (node (ref "JP3") (pin "4") (pinfunction "4_4") (pintype "passive"))
      (node (ref "R17") (pin "2") (pinfunction "2_2") (pintype "passive"))
      (node (ref "R28") (pin "2") (pinfunction "2_2") (pintype "passive"))
    )
    (net (code "4") (name "/1-WIRE") (class "Default")
      (node (ref "JP6") (pin "7") (pinfunction "7_7") (pintype "passive"))
      (node (ref "JP7") (pin "1") (pinfunction "1_1") (pintype "passive"))
    )
    (net (code "5") (name "/3V_REF") (class "Default")
      (node (ref "D1") (pin "3") (pinfunction "C_3") (pintype "passive"))
      (node (ref "IC1") (pin "CH2") (pinfunction "CH2_CH2") (pintype "input"))
      (node (ref "R18") (pin "2") (pinfunction "2_2") (pintype "passive"))
    )
    (net (code "6") (name "/ADC0_1") (class "Default")
      (node (ref "IC3") (pin "CH0") (pinfunction "CH0_CH0") (pintype "input"))
      (node (ref "JP8") (pin "2") (pinfunction "2_2") (pintype "passive"))
    )
    (net (code "7") (name "/ADC0_2") (class "Default")
      (node (ref "IC2") (pin "CH0") (pinfunction "CH0_CH0") (pintype "input"))
      (node (ref "JP8") (pin "9") (pinfunction "9_9") (pintype "passive"))
    )
    (net (code "8") (name "/ADC3_1") (class "Default")
      (node (ref "IC3") (pin "CH3") (pinfunction "CH3_CH3") (pintype "input"))
      (node (ref "JP8") (pin "8") (pinfunction "8_8") (pintype "passive"))
    )
    (net (code "9") (name "/ADC3_2") (class "Default")
      (node (ref "IC2") (pin "CH3") (pinfunction "CH3_CH3") (pintype "input"))
      (node (ref "JP8") (pin "15") (pinfunction "15_15") (pintype "passive"))
    )
    (net (code "10") (name "/ADC4_1") (class "Default")
      (node (ref "IC3") (pin "CH4") (pinfunction "CH4_CH4") (pintype "input"))
      (node (ref "JP8") (pin "1") (pinfunction "1_1") (pintype "passive"))
    )
    (net (code "11") (name "/ADC4_2") (class "Default")
      (node (ref "IC2") (pin "CH4") (pinfunction "CH4_CH4") (pintype "input"))
      (node (ref "JP8") (pin "10") (pinfunction "10_10") (pintype "passive"))
    )
    (net (code "12") (name "/ADC7_1") (class "Default")
      (node (ref "IC3") (pin "CH7") (pinfunction "CH7_CH7") (pintype "input"))
      (node (ref "JP8") (pin "7") (pinfunction "7_7") (pintype "passive"))
    )
    (net (code "13") (name "/ADC7_2") (class "Default")
      (node (ref "IC2") (pin "CH7") (pinfunction "CH7_CH7") (pintype "input"))
      (node (ref "JP8") (pin "16") (pinfunction "16_16") (pintype "passive"))
    )
    (net (code "14") (name "/CS_ANALOG1") (class "Default")
      (node (ref "IC3") (pin "CS") (pinfunction "/CS_CS") (pintype "input"))
      (node (ref "JMP2") (pin "2") (pinfunction "2_2") (pintype "passive"))
    )
    (net (code "15") (name "/CS_ANALOG2") (class "Default")
      (node (ref "IC2") (pin "CS") (pinfunction "/CS_CS") (pintype "input"))
      (node (ref "JMP1") (pin "2") (pinfunction "2_2") (pintype "passive"))
      (node (ref "JMP1") (pin "3") (pinfunction "3_3") (pintype "passive"))
    )
    (net (code "16") (name "/CS_ANALOG3") (class "Default")
      (node (ref "IC1") (pin "CS") (pinfunction "/CS_CS") (pintype "input"))
      (node (ref "JP6") (pin "32") (pinfunction "32_32") (pintype "passive"))
    )
    (net (code "17") (name "/CURR_SNS_0") (class "Default")
      (node (ref "C6") (pin "1") (pinfunction "1_1") (pintype "passive"))
      (node (ref "IC1") (pin "CH1") (pinfunction "CH1_CH1") (pintype "input"))
      (node (ref "R10") (pin "2") (pinfunction "2_2") (pintype "passive"))
    )
    (net (code "18") (name "/CURR_SNS_1") (class "Default")
      (node (ref "C7") (pin "1") (pinfunction "1_1") (pintype "passive"))
      (node (ref "IC1") (pin "CH0") (pinfunction "CH0_CH0") (pintype "input"))
      (node (ref "R11") (pin "2") (pinfunction "2_2") (pintype "passive"))
    )
    (net (code "19") (name "/GPA0_1") (class "Default")
      (node (ref "IC4") (pin "17") (pinfunction "GPA0_17") (pintype "bidirectional"))
      (node (ref "JP12") (pin "16") (pinfunction "16_16") (pintype "passive"))
    )
    (net (code "20") (name "/GPA0_2") (class "Default")
      (node (ref "IC5") (pin "17") (pinfunction "GPA0_17") (pintype "bidirectional"))
      (node (ref "JP13") (pin "16") (pinfunction "16_16") (pintype "passive"))
    )
    (net (code "21") (name "/GPA7_1") (class "Default")
      (node (ref "IC4") (pin "24") (pinfunction "GPA7_24") (pintype "bidirectional"))
      (node (ref "JP12") (pin "2") (pinfunction "2_2") (pintype "passive"))
    )
    (net (code "22") (name "/GPA7_2") (class "Default")
      (node (ref "IC5") (pin "24") (pinfunction "GPA7_24") (pintype "bidirectional"))
      (node (ref "JP13") (pin "2") (pinfunction "2_2") (pintype "passive"))
    )
    (net (code "23") (name "/GPB0_1") (class "Default")
      (node (ref "IC4") (pin "25") (pinfunction "GPB0_25") (pintype "bidirectional"))
      (node (ref "JP12") (pin "1") (pinfunction "1_1") (pintype "passive"))
    )
    (net (code "24") (name "/GPB0_2") (class "Default")
      (node (ref "IC5") (pin "25") (pinfunction "GPB0_25") (pintype "bidirectional"))
      (node (ref "JP13") (pin "1") (pinfunction "1_1") (pintype "passive"))
    )
    (net (code "25") (name "/GPB4_3") (class "Default")
      (node (ref "IC9") (pin "1") (pinfunction "GPB4_1") (pintype "bidirectional"))
      (node (ref "TP5") (pin "TP") (pinfunction "TP_TP") (pintype "input"))
    )
    (net (code "26") (name "/GPB5_3") (class "Default")
      (node (ref "IC9") (pin "2") (pinfunction "GPB5_2") (pintype "bidirectional"))
      (node (ref "TP6") (pin "TP") (pinfunction "TP_TP") (pintype "input"))
    )
    (net (code "27") (name "/GPB6_3") (class "Default")
      (node (ref "IC9") (pin "3") (pinfunction "GPB6_3") (pintype "bidirectional"))
      (node (ref "TP7") (pin "TP") (pinfunction "TP_TP") (pintype "input"))
    )
    (net (code "28") (name "/GPB7_1") (class "Default")
      (node (ref "IC4") (pin "4") (pinfunction "GPB7_4") (pintype "bidirectional"))
      (node (ref "JP12") (pin "15") (pinfunction "15_15") (pintype "passive"))
    )
    (net (code "29") (name "/GPB7_2") (class "Default")
      (node (ref "IC5") (pin "4") (pinfunction "GPB7_4") (pintype "bidirectional"))
      (node (ref "JP13") (pin "15") (pinfunction "15_15") (pintype "passive"))
    )
    (net (code "30") (name "/I2C_CLK") (class "Default")
      (node (ref "IC11") (pin "SCL") (pinfunction "SCL_SCL") (pintype "bidirectional"))
      (node (ref "IC4") (pin "8") (pinfunction "SCL_8") (pintype "input"))
      (node (ref "IC5") (pin "8") (pinfunction "SCL_8") (pintype "input"))
      (node (ref "IC6") (pin "26") (pinfunction "SCL_26") (pintype "bidirectional"))
      (node (ref "IC7") (pin "26") (pinfunction "SCL_26") (pintype "bidirectional"))
      (node (ref "IC8") (pin "24") (pinfunction "PC5(ADC5/SCL)_24") (pintype "bidirectional"))
      (node (ref "IC9") (pin "8") (pinfunction "SCL_8") (pintype "input"))
      (node (ref "JP1") (pin "2") (pinfunction "2_2") (pintype "passive"))
      (node (ref "JP6") (pin "5") (pinfunction "5_5") (pintype "passive"))
    )
    (net (code "31") (name "/I2C_DATA") (class "Default")
      (node (ref "IC11") (pin "SDA") (pinfunction "SDA_SDA") (pintype "bidirectional"))
      (node (ref "IC4") (pin "9") (pinfunction "SDA_9") (pintype "bidirectional"))
      (node (ref "IC5") (pin "9") (pinfunction "SDA_9") (pintype "bidirectional"))
      (node (ref "IC6") (pin "27") (pinfunction "SDA_27") (pintype "bidirectional"))
      (node (ref "IC7") (pin "27") (pinfunction "SDA_27") (pintype "bidirectional"))
      (node (ref "IC8") (pin "23") (pinfunction "PC4(ADC4/SDA)_23") (pintype "bidirectional"))
      (node (ref "IC9") (pin "9") (pinfunction "SDA_9") (pintype "bidirectional"))
      (node (ref "JP1") (pin "1") (pinfunction "1_1") (pintype "passive"))
      (node (ref "JP6") (pin "3") (pinfunction "3_3") (pintype "passive"))
    )
    (net (code "32") (name "/LEAK0") (class "Default")
      (node (ref "IC9") (pin "17") (pinfunction "GPA0_17") (pintype "bidirectional"))
      (node (ref "RN6") (pin "R4B") (pinfunction "4_R4B") (pintype "passive"))
      (node (ref "T1") (pin "C") (pinfunction "C_C") (pintype "passive"))
    )
    (net (code "33") (name "/LEAK1") (class "Default")
      (node (ref "IC9") (pin "18") (pinfunction "GPA1_18") (pintype "bidirectional"))
      (node (ref "RN6") (pin "R3B") (pinfunction "3_R3B") (pintype "passive"))
      (node (ref "T3") (pin "C") (pinfunction "C_C") (pintype "passive"))
    )
    (net (code "34") (name "/LEAK2") (class "Default")
      (node (ref "IC9") (pin "19") (pinfunction "GPA2_19") (pintype "bidirectional"))
      (node (ref "RN6") (pin "R2B") (pinfunction "2_R2B") (pintype "passive"))
      (node (ref "T5") (pin "C") (pinfunction "C_C") (pintype "passive"))
    )
    (net (code "35") (name "/LEAK3") (class "Default")
      (node (ref "IC9") (pin "20") (pinfunction "GPA3_20") (pintype "bidirectional"))
      (node (ref "RN6") (pin "R1B") (pinfunction "1_R1B") (pintype "passive"))
      (node (ref "T7") (pin "C") (pinfunction "C_C") (pintype "passive"))
    )
    (net (code "36") (name "/LEAK4") (class "Default")
      (node (ref "IC9") (pin "21") (pinfunction "GPA4_21") (pintype "bidirectional"))
      (node (ref "RN8") (pin "R4B") (pinfunction "4_R4B") (pintype "passive"))
      (node (ref "T2") (pin "C") (pinfunction "C_C") (pintype "passive"))
    )
    (net (code "37") (name "/LEAK5") (class "Default")
      (node (ref "IC9") (pin "22") (pinfunction "GPA5_22") (pintype "bidirectional"))
      (node (ref "RN8") (pin "R3B") (pinfunction "3_R3B") (pintype "passive"))
      (node (ref "T4") (pin "C") (pinfunction "C_C") (pintype "passive"))
    )
    (net (code "38") (name "/LEAK6") (class "Default")
      (node (ref "IC9") (pin "23") (pinfunction "GPA6_23") (pintype "bidirectional"))
      (node (ref "RN8") (pin "R2B") (pinfunction "2_R2B") (pintype "passive"))
      (node (ref "T6") (pin "C") (pinfunction "C_C") (pintype "passive"))
    )
    (net (code "39") (name "/LEAK7") (class "Default")
      (node (ref "IC9") (pin "24") (pinfunction "GPA7_24") (pintype "bidirectional"))
      (node (ref "RN8") (pin "R1B") (pinfunction "1_R1B") (pintype "passive"))
      (node (ref "T8") (pin "C") (pinfunction "C_C") (pintype "passive"))
    )
    (net (code "40") (name "/LEAK_WARN") (class "Default")
      (node (ref "IC9") (pin "4") (pinfunction "GPB7_4") (pintype "bidirectional"))
      (node (ref "R29") (pin "2") (pinfunction "2_2") (pintype "passive"))
    )
    (net (code "41") (name "/MCP23017_1_A0") (class "Default")
      (node (ref "IC4") (pin "11") (pinfunction "A0_11") (pintype "input"))
      (node (ref "JMP17") (pin "2") (pinfunction "2_2") (pintype "passive"))
    )
    (net (code "42") (name "/MCP23017_1_A1") (class "Default")
      (node (ref "IC4") (pin "12") (pinfunction "A1_12") (pintype "input"))
      (node (ref "JMP15") (pin "2") (pinfunction "2_2") (pintype "passive"))
    )
    (net (code "43") (name "/MCP23017_1_A2") (class "Default")
      (node (ref "IC4") (pin "13") (pinfunction "A2_13") (pintype "input"))
      (node (ref "JMP18") (pin "2") (pinfunction "2_2") (pintype "passive"))
    )
    (net (code "44") (name "/MCP23017_2_A0") (class "Default")
      (node (ref "IC5") (pin "11") (pinfunction "A0_11") (pintype "input"))
      (node (ref "JMP19") (pin "2") (pinfunction "2_2") (pintype "passive"))
    )
    (net (code "45") (name "/MCP23017_2_A1") (class "Default")
      (node (ref "IC5") (pin "12") (pinfunction "A1_12") (pintype "input"))
      (node (ref "JMP16") (pin "2") (pinfunction "2_2") (pintype "passive"))
    )
    (net (code "46") (name "/MCP23017_2_A2") (class "Default")
      (node (ref "IC5") (pin "13") (pinfunction "A2_13") (pintype "input"))
      (node (ref "JMP20") (pin "2") (pinfunction "2_2") (pintype "passive"))
    )
    (net (code "47") (name "/MCP23017_3_A0") (class "Default")
      (node (ref "IC9") (pin "11") (pinfunction "A0_11") (pintype "input"))
      (node (ref "JMP22") (pin "2") (pinfunction "2_2") (pintype "passive"))
    )
    (net (code "48") (name "/MCP23017_3_A1") (class "Default")
      (node (ref "IC9") (pin "12") (pinfunction "A1_12") (pintype "input"))
      (node (ref "JMP21") (pin "2") (pinfunction "2_2") (pintype "passive"))
    )
    (net (code "49") (name "/MCP23017_3_A2") (class "Default")
      (node (ref "IC9") (pin "13") (pinfunction "A2_13") (pintype "input"))
      (node (ref "JMP23") (pin "2") (pinfunction "2_2") (pintype "passive"))
    )
    (net (code "50") (name "/N$17") (class "Default")
      (node (ref "JP6") (pin "29") (pinfunction "29_29") (pintype "passive"))
    )
    (net (code "51") (name "/N$19") (class "Default")
      (node (ref "JP6") (pin "31") (pinfunction "31_31") (pintype "passive"))
    )
    (net (code "52") (name "/N$20") (class "Default")
      (node (ref "JP6") (pin "11") (pinfunction "11_11") (pintype "passive"))
    )
    (net (code "53") (name "/N$21") (class "Default")
      (node (ref "JP6") (pin "13") (pinfunction "13_13") (pintype "passive"))
    )
    (net (code "54") (name "/N$24") (class "Default")
      (node (ref "JP6") (pin "15") (pinfunction "15_15") (pintype "passive"))
    )
    (net (code "55") (name "/N$57") (class "Default")
      (node (ref "JP6") (pin "33") (pinfunction "33_33") (pintype "passive"))
    )
    (net (code "56") (name "/N$59") (class "Default")
      (node (ref "JP6") (pin "35") (pinfunction "35_35") (pintype "passive"))
    )
    (net (code "57") (name "/N$61") (class "Default")
      (node (ref "JP6") (pin "37") (pinfunction "37_37") (pintype "passive"))
    )
    (net (code "58") (name "/N$70") (class "Default")
      (node (ref "JP6") (pin "17") (pinfunction "17_17") (pintype "passive"))
    )
    (net (code "59") (name "/N$90") (class "Default")
      (node (ref "JP6") (pin "36") (pinfunction "36_36") (pintype "passive"))
    )
    (net (code "60") (name "/N$92") (class "Default")
      (node (ref "JP6") (pin "38") (pinfunction "38_38") (pintype "passive"))
    )
    (net (code "61") (name "/N$93") (class "Default")
      (node (ref "JP6") (pin "40") (pinfunction "40_40") (pintype "passive"))
    )
    (net (code "62") (name "/OLED_RST") (class "Default")
      (node (ref "JP6") (pin "27") (pinfunction "27_27") (pintype "passive"))
    )
    (net (code "63") (name "/PCA9685_1_A0") (class "Default")
      (node (ref "IC6") (pin "1") (pinfunction "A0_1") (pintype "bidirectional"))
      (node (ref "JMP3") (pin "1") (pinfunction "1_1") (pintype "passive"))
      (node (ref "JMP3") (pin "2") (pinfunction "2_2") (pintype "passive"))
      (node (ref "RN3") (pin "R2A") (pinfunction "2A_R2A") (pintype "passive"))
    )
    (net (code "64") (name "/PCA9685_1_A1") (class "Default")
      (node (ref "IC6") (pin "2") (pinfunction "A1_2") (pintype "bidirectional"))
      (node (ref "JMP4") (pin "1") (pinfunction "1_1") (pintype "passive"))
      (node (ref "JMP4") (pin "2") (pinfunction "2_2") (pintype "passive"))
      (node (ref "RN3") (pin "R1A") (pinfunction "1A_R1A") (pintype "passive"))
    )
    (net (code "65") (name "/PCA9685_1_A2") (class "Default")
      (node (ref "IC6") (pin "3") (pinfunction "A2_3") (pintype "bidirectional"))
      (node (ref "JMP5") (pin "1") (pinfunction "1_1") (pintype "passive"))
      (node (ref "JMP5") (pin "2") (pinfunction "2_2") (pintype "passive"))
      (node (ref "RN1") (pin "R4A") (pinfunction "4A_R4A") (pintype "passive"))
    )
    (net (code "66") (name "/PCA9685_1_A3") (class "Default")
      (node (ref "IC6") (pin "4") (pinfunction "A3_4") (pintype "bidirectional"))
      (node (ref "JMP6") (pin "1") (pinfunction "1_1") (pintype "passive"))
      (node (ref "JMP6") (pin "2") (pinfunction "2_2") (pintype "passive"))
      (node (ref "RN1") (pin "R3A") (pinfunction "3A_R3A") (pintype "passive"))
    )
    (net (code "67") (name "/PCA9685_1_A4") (class "Default")
      (node (ref "IC6") (pin "5") (pinfunction "A4_5") (pintype "bidirectional"))
      (node (ref "JMP7") (pin "1") (pinfunction "1_1") (pintype "passive"))
      (node (ref "JMP7") (pin "2") (pinfunction "2_2") (pintype "passive"))
      (node (ref "RN1") (pin "R2A") (pinfunction "2A_R2A") (pintype "passive"))
    )
    (net (code "68") (name "/PCA9685_1_A5") (class "Default")
      (node (ref "IC6") (pin "24") (pinfunction "A5_24") (pintype "bidirectional"))
      (node (ref "JMP8") (pin "1") (pinfunction "1_1") (pintype "passive"))
      (node (ref "JMP8") (pin "2") (pinfunction "2_2") (pintype "passive"))
      (node (ref "RN1") (pin "R1A") (pinfunction "1A_R1A") (pintype "passive"))
    )
    (net (code "69") (name "/PCA9685_1_PWM0") (class "Default")
      (node (ref "IC6") (pin "6") (pinfunction "PWM0_6") (pintype "output"))
      (node (ref "RN10") (pin "R4B") (pinfunction "4_R4B") (pintype "passive"))
    )
    (net (code "70") (name "/PCA9685_1_PWM1") (class "Default")
      (node (ref "IC6") (pin "7") (pinfunction "PWM1_7") (pintype "output"))
      (node (ref "RN10") (pin "R3B") (pinfunction "3_R3B") (pintype "passive"))
    )
    (net (code "71") (name "/PCA9685_1_PWM2") (class "Default")
      (node (ref "IC6") (pin "8") (pinfunction "PWM2_8") (pintype "output"))
      (node (ref "RN10") (pin "R2B") (pinfunction "2_R2B") (pintype "passive"))
    )
    (net (code "72") (name "/PCA9685_1_PWM3") (class "Default")
      (node (ref "IC6") (pin "9") (pinfunction "PWM3_9") (pintype "output"))
      (node (ref "RN10") (pin "R1B") (pinfunction "1_R1B") (pintype "passive"))
    )
    (net (code "73") (name "/PCA9685_1_PWM4") (class "Default")
      (node (ref "IC6") (pin "10") (pinfunction "PWM4_10") (pintype "output"))
      (node (ref "RN9") (pin "R4B") (pinfunction "4_R4B") (pintype "passive"))
    )
    (net (code "74") (name "/PCA9685_1_PWM5") (class "Default")
      (node (ref "IC6") (pin "11") (pinfunction "PWM5_11") (pintype "output"))
      (node (ref "RN9") (pin "R3B") (pinfunction "3_R3B") (pintype "passive"))
    )
    (net (code "75") (name "/PCA9685_1_PWM6") (class "Default")
      (node (ref "IC6") (pin "12") (pinfunction "PWM6_12") (pintype "output"))
      (node (ref "RN9") (pin "R2B") (pinfunction "2_R2B") (pintype "passive"))
    )
    (net (code "76") (name "/PCA9685_1_PWM7") (class "Default")
      (node (ref "IC6") (pin "13") (pinfunction "PWM7_13") (pintype "output"))
      (node (ref "RN9") (pin "R1B") (pinfunction "1_R1B") (pintype "passive"))
    )
    (net (code "77") (name "/PCA9685_1_PWM8") (class "Default")
      (node (ref "IC6") (pin "15") (pinfunction "PWM8_15") (pintype "output"))
      (node (ref "RN13") (pin "R4B") (pinfunction "4_R4B") (pintype "passive"))
    )
    (net (code "78") (name "/PCA9685_1_PWM9") (class "Default")
      (node (ref "IC6") (pin "16") (pinfunction "PWM9_16") (pintype "output"))
      (node (ref "RN13") (pin "R3B") (pinfunction "3_R3B") (pintype "passive"))
    )
    (net (code "79") (name "/PCA9685_1_PWM10") (class "Default")
      (node (ref "IC6") (pin "17") (pinfunction "PWM10_17") (pintype "output"))
      (node (ref "RN13") (pin "R2B") (pinfunction "2_R2B") (pintype "passive"))
    )
    (net (code "80") (name "/PCA9685_1_PWM11") (class "Default")
      (node (ref "IC6") (pin "18") (pinfunction "PWM11_18") (pintype "output"))
      (node (ref "RN13") (pin "R1B") (pinfunction "1_R1B") (pintype "passive"))
    )
    (net (code "81") (name "/PCA9685_1_PWM12") (class "Default")
      (node (ref "IC6") (pin "19") (pinfunction "PWM12_19") (pintype "output"))
      (node (ref "RN14") (pin "R4B") (pinfunction "4_R4B") (pintype "passive"))
    )
    (net (code "82") (name "/PCA9685_1_PWM13") (class "Default")
      (node (ref "IC6") (pin "20") (pinfunction "PWM13_20") (pintype "output"))
      (node (ref "RN14") (pin "R3B") (pinfunction "3_R3B") (pintype "passive"))
    )
    (net (code "83") (name "/PCA9685_1_PWM14") (class "Default")
      (node (ref "IC6") (pin "21") (pinfunction "PWM14_21") (pintype "output"))
      (node (ref "RN14") (pin "R2B") (pinfunction "2_R2B") (pintype "passive"))
    )
    (net (code "84") (name "/PCA9685_1_PWM15") (class "Default")
      (node (ref "IC6") (pin "22") (pinfunction "PWM15_22") (pintype "output"))
      (node (ref "RN14") (pin "R1B") (pinfunction "1_R1B") (pintype "passive"))
    )
    (net (code "85") (name "/PCA9685_2_A0") (class "Default")
      (node (ref "IC7") (pin "1") (pinfunction "A0_1") (pintype "bidirectional"))
      (node (ref "JMP9") (pin "1") (pinfunction "1_1") (pintype "passive"))
      (node (ref "JMP9") (pin "2") (pinfunction "2_2") (pintype "passive"))
      (node (ref "RN4") (pin "R2A") (pinfunction "2A_R2A") (pintype "passive"))
    )
    (net (code "86") (name "/PCA9685_2_A1") (class "Default")
      (node (ref "IC7") (pin "2") (pinfunction "A1_2") (pintype "bidirectional"))
      (node (ref "JMP10") (pin "1") (pinfunction "1_1") (pintype "passive"))
      (node (ref "JMP10") (pin "2") (pinfunction "2_2") (pintype "passive"))
      (node (ref "RN4") (pin "R1A") (pinfunction "1A_R1A") (pintype "passive"))
    )
    (net (code "87") (name "/PCA9685_2_A2") (class "Default")
      (node (ref "IC7") (pin "3") (pinfunction "A2_3") (pintype "bidirectional"))
      (node (ref "JMP11") (pin "1") (pinfunction "1_1") (pintype "passive"))
      (node (ref "JMP11") (pin "2") (pinfunction "2_2") (pintype "passive"))
      (node (ref "RN2") (pin "R4A") (pinfunction "4A_R4A") (pintype "passive"))
    )
    (net (code "88") (name "/PCA9685_2_A3") (class "Default")
      (node (ref "IC7") (pin "4") (pinfunction "A3_4") (pintype "bidirectional"))
      (node (ref "JMP12") (pin "1") (pinfunction "1_1") (pintype "passive"))
      (node (ref "JMP12") (pin "2") (pinfunction "2_2") (pintype "passive"))
      (node (ref "RN2") (pin "R3A") (pinfunction "3A_R3A") (pintype "passive"))
    )
    (net (code "89") (name "/PCA9685_2_A4") (class "Default")
      (node (ref "IC7") (pin "5") (pinfunction "A4_5") (pintype "bidirectional"))
      (node (ref "JMP13") (pin "1") (pinfunction "1_1") (pintype "passive"))
      (node (ref "JMP13") (pin "2") (pinfunction "2_2") (pintype "passive"))
      (node (ref "RN2") (pin "R2A") (pinfunction "2A_R2A") (pintype "passive"))
    )
    (net (code "90") (name "/PCA9685_2_A5") (class "Default")
      (node (ref "IC7") (pin "24") (pinfunction "A5_24") (pintype "bidirectional"))
      (node (ref "JMP14") (pin "1") (pinfunction "1_1") (pintype "passive"))
      (node (ref "JMP14") (pin "2") (pinfunction "2_2") (pintype "passive"))
      (node (ref "RN2") (pin "R1A") (pinfunction "1A_R1A") (pintype "passive"))
    )
    (net (code "91") (name "/PCA9685_2_PWM0") (class "Default")
      (node (ref "IC7") (pin "6") (pinfunction "PWM0_6") (pintype "output"))
      (node (ref "RN12") (pin "R4B") (pinfunction "4_R4B") (pintype "passive"))
    )
    (net (code "92") (name "/PCA9685_2_PWM1") (class "Default")
      (node (ref "IC7") (pin "7") (pinfunction "PWM1_7") (pintype "output"))
      (node (ref "RN12") (pin "R3B") (pinfunction "3_R3B") (pintype "passive"))
    )
    (net (code "93") (name "/PCA9685_2_PWM2") (class "Default")
      (node (ref "IC7") (pin "8") (pinfunction "PWM2_8") (pintype "output"))
      (node (ref "RN12") (pin "R2B") (pinfunction "2_R2B") (pintype "passive"))
    )
    (net (code "94") (name "/PCA9685_2_PWM3") (class "Default")
      (node (ref "IC7") (pin "9") (pinfunction "PWM3_9") (pintype "output"))
      (node (ref "RN12") (pin "R1B") (pinfunction "1_R1B") (pintype "passive"))
    )
    (net (code "95") (name "/PCA9685_2_PWM4") (class "Default")
      (node (ref "IC7") (pin "10") (pinfunction "PWM4_10") (pintype "output"))
      (node (ref "RN11") (pin "R4B") (pinfunction "4_R4B") (pintype "passive"))
    )
    (net (code "96") (name "/PCA9685_2_PWM5") (class "Default")
      (node (ref "IC7") (pin "11") (pinfunction "PWM5_11") (pintype "output"))
      (node (ref "RN11") (pin "R3B") (pinfunction "3_R3B") (pintype "passive"))
    )
    (net (code "97") (name "/PCA9685_2_PWM6") (class "Default")
      (node (ref "IC7") (pin "12") (pinfunction "PWM6_12") (pintype "output"))
      (node (ref "RN11") (pin "R2B") (pinfunction "2_R2B") (pintype "passive"))
    )
    (net (code "98") (name "/PCA9685_2_PWM7") (class "Default")
      (node (ref "IC7") (pin "13") (pinfunction "PWM7_13") (pintype "output"))
      (node (ref "RN11") (pin "R1B") (pinfunction "1_R1B") (pintype "passive"))
    )
    (net (code "99") (name "/PCA9685_2_PWM8") (class "Default")
      (node (ref "IC7") (pin "15") (pinfunction "PWM8_15") (pintype "output"))
      (node (ref "RN15") (pin "R4B") (pinfunction "4_R4B") (pintype "passive"))
    )
    (net (code "100") (name "/PCA9685_2_PWM9") (class "Default")
      (node (ref "IC7") (pin "16") (pinfunction "PWM9_16") (pintype "output"))
      (node (ref "RN15") (pin "R3B") (pinfunction "3_R3B") (pintype "passive"))
    )
    (net (code "101") (name "/PCA9685_2_PWM10") (class "Default")
      (node (ref "IC7") (pin "17") (pinfunction "PWM10_17") (pintype "output"))
      (node (ref "RN15") (pin "R2B") (pinfunction "2_R2B") (pintype "passive"))
    )
    (net (code "102") (name "/PCA9685_2_PWM11") (class "Default")
      (node (ref "IC7") (pin "18") (pinfunction "PWM11_18") (pintype "output"))
      (node (ref "RN15") (pin "R1B") (pinfunction "1_R1B") (pintype "passive"))
    )
    (net (code "103") (name "/PCA9685_2_PWM12") (class "Default")
      (node (ref "IC7") (pin "19") (pinfunction "PWM12_19") (pintype "output"))
      (node (ref "RN16") (pin "R4B") (pinfunction "4_R4B") (pintype "passive"))
    )
    (net (code "104") (name "/PCA9685_2_PWM13") (class "Default")
      (node (ref "IC7") (pin "20") (pinfunction "PWM13_20") (pintype "output"))
      (node (ref "RN16") (pin "R3B") (pinfunction "3_R3B") (pintype "passive"))
    )
    (net (code "105") (name "/PCA9685_2_PWM14") (class "Default")
      (node (ref "IC7") (pin "21") (pinfunction "PWM14_21") (pintype "output"))
      (node (ref "RN16") (pin "R2B") (pinfunction "2_R2B") (pintype "passive"))
    )
    (net (code "106") (name "/PCA9685_2_PWM15") (class "Default")
      (node (ref "IC7") (pin "22") (pinfunction "PWM15_22") (pintype "output"))
      (node (ref "RN16") (pin "R1B") (pinfunction "1_R1B") (pintype "passive"))
    )
    (net (code "107") (name "/PCA9685_OE") (class "Default")
      (node (ref "IC6") (pin "23") (pinfunction "#OE_23") (pintype "input"))
      (node (ref "IC7") (pin "23") (pinfunction "#OE_23") (pintype "input"))
      (node (ref "JP6") (pin "28") (pinfunction "28_28") (pintype "passive"))
      (node (ref "RN3") (pin "R3A") (pinfunction "3A_R3A") (pintype "passive"))
      (node (ref "RN4") (pin "R3A") (pinfunction "3A_R3A") (pintype "passive"))
    )
    (net (code "108") (name "/PWR0") (class "Default")
      (node (ref "IC9") (pin "25") (pinfunction "GPB0_25") (pintype "bidirectional"))
      (node (ref "R2") (pin "1") (pinfunction "1_1") (pintype "passive"))
    )
    (net (code "109") (name "/PWR1") (class "Default")
      (node (ref "IC9") (pin "26") (pinfunction "GPB1_26") (pintype "bidirectional"))
      (node (ref "R4") (pin "1") (pinfunction "1_1") (pintype "passive"))
    )
    (net (code "110") (name "/PWR2") (class "Default")
      (node (ref "IC9") (pin "27") (pinfunction "GPB2_27") (pintype "bidirectional"))
      (node (ref "R6") (pin "1") (pinfunction "1_1") (pintype "passive"))
    )
    (net (code "111") (name "/PWR3") (class "Default")
      (node (ref "IC9") (pin "28") (pinfunction "GPB3_28") (pintype "bidirectional"))
      (node (ref "R8") (pin "1") (pinfunction "1_1") (pintype "passive"))
    )
    (net (code "112") (name "/PWR_IN") (class "Default")
      (node (ref "Q1") (pin "D0") (pinfunction "DRAIN_D0") (pintype "bidirectional"))
      (node (ref "Q1") (pin "D1") (pinfunction "DRAIN_D1") (pintype "bidirectional"))
      (node (ref "Q1") (pin "D2") (pinfunction "DRAIN_D2") (pintype "bidirectional"))
      (node (ref "Q1") (pin "D3") (pinfunction "DRAIN_D3") (pintype "bidirectional"))
      (node (ref "Q1") (pin "D4") (pinfunction "DRAIN_D4") (pintype "bidirectional"))
      (node (ref "X1") (pin "1") (pinfunction "KL_1") (pintype "passive"))
      (node (ref "X2") (pin "1") (pinfunction "KL_1") (pintype "passive"))
      (node (ref "X3") (pin "1") (pinfunction "KL_1") (pintype "passive"))
      (node (ref "X4") (pin "1") (pinfunction "KL_1") (pintype "passive"))
      (node (ref "X5") (pin "1") (pinfunction "KL_1") (pintype "passive"))
    )
    (net (code "113") (name "/RESET") (class "Default")
      (node (ref "IC8") (pin "25") (pinfunction "PC6(/RESET)_25") (pintype "bidirectional"))
      (node (ref "JP15") (pin "5") (pinfunction "5_5") (pintype "passive"))
      (node (ref "PB1") (pin "2") (pinfunction "2_2") (pintype "passive"))
      (node (ref "R25") (pin "1") (pinfunction "1_1") (pintype "passive"))
    )
    (net (code "114") (name "/SPI_CE0") (class "Default")
      (node (ref "JMP2") (pin "1") (pinfunction "1_1") (pintype "passive"))
      (node (ref "JP6") (pin "24") (pinfunction "24_24") (pintype "passive"))
    )
    (net (code "115") (name "/SPI_CE1") (class "Default")
      (node (ref "JMP1") (pin "1") (pinfunction "1_1") (pintype "passive"))
      (node (ref "JP6") (pin "26") (pinfunction "26_26") (pintype "passive"))
    )
    (net (code "116") (name "/SPI_CLK") (class "Default")
      (node (ref "IC1") (pin "CLK") (pinfunction "CLK_CLK") (pintype "input"))
      (node (ref "IC2") (pin "CLK") (pinfunction "CLK_CLK") (pintype "input"))
      (node (ref "IC3") (pin "CLK") (pinfunction "CLK_CLK") (pintype "input"))
      (node (ref "JP4") (pin "1") (pinfunction "1_1") (pintype "passive"))
      (node (ref "JP6") (pin "23") (pinfunction "23_23") (pintype "passive"))
    )
    (net (code "117") (name "/SPI_CS_1") (class "Default")
      (node (ref "JP5") (pin "4") (pinfunction "4_4") (pintype "passive"))
      (node (ref "JP6") (pin "12") (pinfunction "12_12") (pintype "passive"))
    )
    (net (code "118") (name "/SPI_CS_2") (class "Default")
      (node (ref "JP5") (pin "3") (pinfunction "3_3") (pintype "passive"))
      (node (ref "JP6") (pin "16") (pinfunction "16_16") (pintype "passive"))
    )
    (net (code "119") (name "/SPI_CS_3") (class "Default")
      (node (ref "JP5") (pin "2") (pinfunction "2_2") (pintype "passive"))
      (node (ref "JP6") (pin "18") (pinfunction "18_18") (pintype "passive"))
    )
    (net (code "120") (name "/SPI_CS_4") (class "Default")
      (node (ref "JP5") (pin "1") (pinfunction "1_1") (pintype "passive"))
      (node (ref "JP6") (pin "22") (pinfunction "22_22") (pintype "passive"))
    )
    (net (code "121") (name "/SPI_MISO") (class "Default")
      (node (ref "IC1") (pin "DOUT") (pinfunction "DOUT_DOUT") (pintype "output"))
      (node (ref "IC2") (pin "DOUT") (pinfunction "DOUT_DOUT") (pintype "output"))
      (node (ref "IC3") (pin "DOUT") (pinfunction "DOUT_DOUT") (pintype "output"))
      (node (ref "JP4") (pin "3") (pinfunction "3_3") (pintype "passive"))
      (node (ref "JP6") (pin "21") (pinfunction "21_21") (pintype "passive"))
    )
    (net (code "122") (name "/SPI_MOSI") (class "Default")
      (node (ref "IC1") (pin "DIN") (pinfunction "DIN_DIN") (pintype "input"))
      (node (ref "IC2") (pin "DIN") (pinfunction "DIN_DIN") (pintype "input"))
      (node (ref "IC3") (pin "DIN") (pinfunction "DIN_DIN") (pintype "input"))
      (node (ref "JP4") (pin "2") (pinfunction "2_2") (pintype "passive"))
      (node (ref "JP6") (pin "19") (pinfunction "19_19") (pintype "passive"))
    )
    (net (code "123") (name "/TEMP_AMB") (class "Default")
      (node (ref "IC1") (pin "CH3") (pinfunction "CH3_CH3") (pintype "input"))
      (node (ref "IC10") (pin "2") (pinfunction "VOUT_2") (pintype "bidirectional"))
    )
    (net (code "124") (name "/UART_RXD") (class "Default")
      (node (ref "JP2") (pin "1") (pinfunction "1_1") (pintype "passive"))
      (node (ref "JP6") (pin "10") (pinfunction "10_10") (pintype "passive"))
    )
    (net (code "125") (name "/UART_TXD") (class "Default")
      (node (ref "JP2") (pin "2") (pinfunction "2_2") (pintype "passive"))
      (node (ref "JP6") (pin "8") (pinfunction "8_8") (pintype "passive"))
    )
    (net (code "126") (name "A0") (class "Default")
      (node (ref "IC8") (pin "19") (pinfunction "PC0(ADC0)_19") (pintype "bidirectional"))
      (node (ref "JP14") (pin "1") (pinfunction "1_1") (pintype "passive"))
    )
    (net (code "127") (name "A1") (class "Default")
      (node (ref "IC8") (pin "20") (pinfunction "PC1(ADC1)_20") (pintype "bidirectional"))
      (node (ref "JP14") (pin "2") (pinfunction "2_2") (pintype "passive"))
    )
    (net (code "128") (name "A2") (class "Default")
      (node (ref "IC8") (pin "21") (pinfunction "PC2(ADC2)_21") (pintype "bidirectional"))
      (node (ref "JP14") (pin "3") (pinfunction "3_3") (pintype "passive"))
    )
    (net (code "129") (name "A3") (class "Default")
      (node (ref "IC8") (pin "22") (pinfunction "PC3(ADC3)_22") (pintype "bidirectional"))
      (node (ref "JP14") (pin "4") (pinfunction "4_4") (pintype "passive"))
    )
    (net (code "130") (name "D2") (class "Default")
      (node (ref "IC8") (pin "28") (pinfunction "PD2(INT0)_28") (pintype "bidirectional"))
      (node (ref "JP16") (pin "6") (pinfunction "6_6") (pintype "passive"))
    )
    (net (code "131") (name "D3") (class "Default")
      (node (ref "IC8") (pin "1") (pinfunction "PD3(INT1)_1") (pintype "bidirectional"))
      (node (ref "JP16") (pin "4") (pinfunction "4_4") (pintype "passive"))
    )
    (net (code "132") (name "D4") (class "Default")
      (node (ref "IC8") (pin "2") (pinfunction "PD4(XCK/T0)_2") (pintype "bidirectional"))
      (node (ref "S1") (pin "5") (pinfunction "5_5") (pintype "passive"))
    )
    (net (code "133") (name "D5") (class "Default")
      (node (ref "IC8") (pin "7") (pinfunction "PD5(T1)_7") (pintype "bidirectional"))
      (node (ref "S1") (pin "6") (pinfunction "6_6") (pintype "passive"))
    )
    (net (code "134") (name "D6") (class "Default")
      (node (ref "IC8") (pin "8") (pinfunction "PD6(AIN0)_8") (pintype "bidirectional"))
      (node (ref "S1") (pin "7") (pinfunction "7_7") (pintype "passive"))
    )
    (net (code "135") (name "D7") (class "Default")
      (node (ref "IC8") (pin "9") (pinfunction "PD7(AIN1)_9") (pintype "bidirectional"))
      (node (ref "S1") (pin "8") (pinfunction "8_8") (pintype "passive"))
    )
    (net (code "136") (name "D8") (class "Default")
      (node (ref "IC8") (pin "10") (pinfunction "PB0(ICP)_10") (pintype "bidirectional"))
      (node (ref "JP16") (pin "2") (pinfunction "2_2") (pintype "passive"))
    )
    (net (code "137") (name "D9") (class "Default")
      (node (ref "IC8") (pin "11") (pinfunction "PB1(OC1A)_11") (pintype "bidirectional"))
      (node (ref "JP16") (pin "1") (pinfunction "1_1") (pintype "passive"))
    )
    (net (code "138") (name "D10") (class "Default")
      (node (ref "IC8") (pin "12") (pinfunction "PB2(SS/OC1B)_12") (pintype "bidirectional"))
      (node (ref "JP16") (pin "3") (pinfunction "3_3") (pintype "passive"))
    )
    (net (code "139") (name "D11") (class "Default")
      (node (ref "IC8") (pin "13") (pinfunction "PB3(MOSI/OC2)_13") (pintype "bidirectional"))
      (node (ref "JP15") (pin "4") (pinfunction "4_4") (pintype "passive"))
      (node (ref "JP16") (pin "5") (pinfunction "5_5") (pintype "passive"))
    )
    (net (code "140") (name "D12") (class "Default")
      (node (ref "IC8") (pin "14") (pinfunction "PB4(MISO)_14") (pintype "bidirectional"))
      (node (ref "JP15") (pin "1") (pinfunction "1_1") (pintype "passive"))
      (node (ref "JP16") (pin "7") (pinfunction "7_7") (pintype "passive"))
    )
    (net (code "141") (name "D13") (class "Default")
      (node (ref "IC8") (pin "15") (pinfunction "PB5(SCK)_15") (pintype "bidirectional"))
      (node (ref "JP15") (pin "3") (pinfunction "3_3") (pintype "passive"))
      (node (ref "JP16") (pin "9") (pinfunction "9_9") (pintype "passive"))
      (node (ref "R26") (pin "1") (pinfunction "1_1") (pintype "passive"))
    )
    (net (code "142") (name "GND") (class "Default")
      (node (ref "C1") (pin "-") (pinfunction "-_-") (pintype "passive"))
      (node (ref "C10") (pin "2") (pinfunction "2_2") (pintype "passive"))
      (node (ref "C11") (pin "2") (pinfunction "2_2") (pintype "passive"))
      (node (ref "C12") (pin "2") (pinfunction "2_2") (pintype "passive"))
      (node (ref "C13") (pin "2") (pinfunction "2_2") (pintype "passive"))
      (node (ref "C14") (pin "2") (pinfunction "2_2") (pintype "passive"))
      (node (ref "C15") (pin "2") (pinfunction "2_2") (pintype "passive"))
      (node (ref "C16") (pin "2") (pinfunction "2_2") (pintype "passive"))
      (node (ref "C17") (pin "1") (pinfunction "1_1") (pintype "passive"))
      (node (ref "C2") (pin "-") (pinfunction "-_-") (pintype "passive"))
      (node (ref "C3") (pin "2") (pinfunction "2_2") (pintype "passive"))
      (node (ref "C4") (pin "2") (pinfunction "2_2") (pintype "passive"))
      (node (ref "C5") (pin "2") (pinfunction "2_2") (pintype "passive"))
      (node (ref "C6") (pin "2") (pinfunction "2_2") (pintype "passive"))
      (node (ref "C7") (pin "2") (pinfunction "2_2") (pintype "passive"))
      (node (ref "C8") (pin "2") (pinfunction "2_2") (pintype "passive"))
      (node (ref "C9") (pin "2") (pinfunction "2_2") (pintype "passive"))
      (node (ref "D1") (pin "1") (pinfunction "A_1") (pintype "passive"))
      (node (ref "IC1") (pin "AGND") (pinfunction "AGND_AGND") (pintype "power_in"))
      (node (ref "IC1") (pin "DGND") (pinfunction "GND_DGND") (pintype "power_in"))
      (node (ref "IC10") (pin "3") (pinfunction "GND_3") (pintype "bidirectional"))
      (node (ref "IC11") (pin "GND") (pinfunction "GND_GND") (pintype "bidirectional"))
      (node (ref "IC12") (pin "2") (pinfunction "GND_2") (pintype "bidirectional"))
      (node (ref "IC12") (pin "4") (pinfunction "GND_4") (pintype "bidirectional"))
      (node (ref "IC12") (pin "7") (pinfunction "GND_7") (pintype "bidirectional"))
      (node (ref "IC13") (pin "2") (pinfunction "GND_2") (pintype "bidirectional"))
      (node (ref "IC13") (pin "4") (pinfunction "GND_4") (pintype "bidirectional"))
      (node (ref "IC13") (pin "7") (pinfunction "GND_7") (pintype "bidirectional"))
      (node (ref "IC2") (pin "AGND") (pinfunction "AGND_AGND") (pintype "power_in"))
      (node (ref "IC2") (pin "DGND") (pinfunction "GND_DGND") (pintype "power_in"))
      (node (ref "IC3") (pin "AGND") (pinfunction "AGND_AGND") (pintype "power_in"))
      (node (ref "IC3") (pin "DGND") (pinfunction "GND_DGND") (pintype "power_in"))
      (node (ref "IC4") (pin "6") (pinfunction "VSS_6") (pintype "power_in"))
      (node (ref "IC5") (pin "6") (pinfunction "VSS_6") (pintype "power_in"))
      (node (ref "IC6") (pin "14") (pinfunction "GND_14") (pintype "power_in"))
      (node (ref "IC6") (pin "25") (pinfunction "EXTCLK_25") (pintype "input"))
      (node (ref "IC7") (pin "14") (pinfunction "GND_14") (pintype "power_in"))
      (node (ref "IC7") (pin "25") (pinfunction "EXTCLK_25") (pintype "input"))
      (node (ref "IC8") (pin "18") (pinfunction "GND_18") (pintype "bidirectional"))
      (node (ref "IC8") (pin "4") (pinfunction "GND_4") (pintype "bidirectional"))
      (node (ref "IC8") (pin "PAD") (pinfunction "GND_PAD") (pintype "bidirectional"))
      (node (ref "IC9") (pin "6") (pinfunction "VSS_6") (pintype "power_in"))
      (node (ref "IC9") (pin "EXP") (pinfunction "VSS_EXP") (pintype "power_in"))
      (node (ref "JMP15") (pin "3") (pinfunction "3_3") (pintype "passive"))
      (node (ref "JMP16") (pin "3") (pinfunction "3_3") (pintype "passive"))
      (node (ref "JMP17") (pin "3") (pinfunction "3_3") (pintype "passive"))
      (node (ref "JMP18") (pin "3") (pinfunction "3_3") (pintype "passive"))
      (node (ref "JMP19") (pin "3") (pinfunction "3_3") (pintype "passive"))
      (node (ref "JMP20") (pin "3") (pinfunction "3_3") (pintype "passive"))
      (node (ref "JMP21") (pin "3") (pinfunction "3_3") (pintype "passive"))
      (node (ref "JMP22") (pin "3") (pinfunction "3_3") (pintype "passive"))
      (node (ref "JMP23") (pin "3") (pinfunction "3_3") (pintype "passive"))
      (node (ref "JP15") (pin "6") (pinfunction "6_6") (pintype "passive"))
      (node (ref "JP3") (pin "1") (pinfunction "1_1") (pintype "passive"))
      (node (ref "JP3") (pin "2") (pinfunction "2_2") (pintype "passive"))
      (node (ref "JP6") (pin "14") (pinfunction "14_14") (pintype "passive"))
      (node (ref "JP6") (pin "20") (pinfunction "20_20") (pintype "passive"))
      (node (ref "JP6") (pin "25") (pinfunction "25_25") (pintype "passive"))
      (node (ref "JP6") (pin "30") (pinfunction "30_30") (pintype "passive"))
      (node (ref "JP6") (pin "34") (pinfunction "34_34") (pintype "passive"))
      (node (ref "JP6") (pin "39") (pinfunction "39_39") (pintype "passive"))
      (node (ref "JP6") (pin "6") (pinfunction "6_6") (pintype "passive"))
      (node (ref "JP6") (pin "9") (pinfunction "9_9") (pintype "passive"))
      (node (ref "LEAK1") (pin "2") (pinfunction "2_2") (pintype "bidirectional"))
      (node (ref "LEAK1") (pin "BASE0") (pinfunction "BASE_BASE0") (pintype "bidirectional"))
      (node (ref "LEAK1") (pin "BASE1") (pinfunction "BASE_BASE1") (pintype "bidirectional"))
      (node (ref "LEAK2") (pin "2") (pinfunction "2_2") (pintype "bidirectional"))
      (node (ref "LEAK2") (pin "BASE0") (pinfunction "BASE_BASE0") (pintype "bidirectional"))
      (node (ref "LEAK2") (pin "BASE1") (pinfunction "BASE_BASE1") (pintype "bidirectional"))
      (node (ref "LEAK3") (pin "2") (pinfunction "2_2") (pintype "bidirectional"))
      (node (ref "LEAK3") (pin "BASE0") (pinfunction "BASE_BASE0") (pintype "bidirectional"))
      (node (ref "LEAK3") (pin "BASE1") (pinfunction "BASE_BASE1") (pintype "bidirectional"))
      (node (ref "LEAK4") (pin "2") (pinfunction "2_2") (pintype "bidirectional"))
      (node (ref "LEAK4") (pin "BASE0") (pinfunction "BASE_BASE0") (pintype "bidirectional"))
      (node (ref "LEAK4") (pin "BASE1") (pinfunction "BASE_BASE1") (pintype "bidirectional"))
      (node (ref "LEAK5") (pin "2") (pinfunction "2_2") (pintype "bidirectional"))
      (node (ref "LEAK5") (pin "BASE0") (pinfunction "BASE_BASE0") (pintype "bidirectional"))
      (node (ref "LEAK5") (pin "BASE1") (pinfunction "BASE_BASE1") (pintype "bidirectional"))
      (node (ref "LEAK6") (pin "2") (pinfunction "2_2") (pintype "bidirectional"))
      (node (ref "LEAK6") (pin "BASE0") (pinfunction "BASE_BASE0") (pintype "bidirectional"))
      (node (ref "LEAK6") (pin "BASE1") (pinfunction "BASE_BASE1") (pintype "bidirectional"))
      (node (ref "LEAK7") (pin "2") (pinfunction "2_2") (pintype "bidirectional"))
      (node (ref "LEAK7") (pin "BASE0") (pinfunction "BASE_BASE0") (pintype "bidirectional"))
      (node (ref "LEAK7") (pin "BASE1") (pinfunction "BASE_BASE1") (pintype "bidirectional"))
      (node (ref "LEAK8") (pin "2") (pinfunction "2_2") (pintype "bidirectional"))
      (node (ref "LEAK8") (pin "BASE0") (pinfunction "BASE_BASE0") (pintype "bidirectional"))
      (node (ref "LEAK8") (pin "BASE1") (pinfunction "BASE_BASE1") (pintype "bidirectional"))
      (node (ref "LED1") (pin "C") (pinfunction "C_C") (pintype "passive"))
      (node (ref "LED2") (pin "C") (pinfunction "C_C") (pintype "passive"))
      (node (ref "LED3") (pin "C") (pinfunction "C_C") (pintype "passive"))
      (node (ref "LED4") (pin "C") (pinfunction "C_C") (pintype "passive"))
      (node (ref "PB1") (pin "1") (pinfunction "1_1") (pintype "passive"))
      (node (ref "Q2") (pin "S1") (pinfunction "SOURCE_S1") (pintype "bidirectional"))
      (node (ref "Q2") (pin "S2") (pinfunction "SOURCE_S2") (pintype "bidirectional"))
      (node (ref "Q2") (pin "S3") (pinfunction "SOURCE_S3") (pintype "bidirectional"))
      (node (ref "Q3") (pin "S1") (pinfunction "SOURCE_S1") (pintype "bidirectional"))
      (node (ref "Q3") (pin "S2") (pinfunction "SOURCE_S2") (pintype "bidirectional"))
      (node (ref "Q3") (pin "S3") (pinfunction "SOURCE_S3") (pintype "bidirectional"))
      (node (ref "Q4") (pin "S1") (pinfunction "SOURCE_S1") (pintype "bidirectional"))
      (node (ref "Q4") (pin "S2") (pinfunction "SOURCE_S2") (pintype "bidirectional"))
      (node (ref "Q4") (pin "S3") (pinfunction "SOURCE_S3") (pintype "bidirectional"))
      (node (ref "Q5") (pin "S1") (pinfunction "SOURCE_S1") (pintype "bidirectional"))
      (node (ref "Q5") (pin "S2") (pinfunction "SOURCE_S2") (pintype "bidirectional"))
      (node (ref "Q5") (pin "S3") (pinfunction "SOURCE_S3") (pintype "bidirectional"))
      (node (ref "R1") (pin "2") (pinfunction "2_2") (pintype "passive"))
      (node (ref "R13") (pin "1") (pinfunction "1_1") (pintype "passive"))
      (node (ref "R15") (pin "1") (pinfunction "1_1") (pintype "passive"))
      (node (ref "R3") (pin "1") (pinfunction "1_1") (pintype "passive"))
      (node (ref "R5") (pin "1") (pinfunction "1_1") (pintype "passive"))
      (node (ref "R7") (pin "1") (pinfunction "1_1") (pintype "passive"))
      (node (ref "R9") (pin "1") (pinfunction "1_1") (pintype "passive"))
      (node (ref "RN1") (pin "R1B") (pinfunction "1_R1B") (pintype "passive"))
      (node (ref "RN1") (pin "R2B") (pinfunction "2_R2B") (pintype "passive"))
      (node (ref "RN1") (pin "R3B") (pinfunction "3_R3B") (pintype "passive"))
      (node (ref "RN1") (pin "R4B") (pinfunction "4_R4B") (pintype "passive"))
      (node (ref "RN2") (pin "R1B") (pinfunction "1_R1B") (pintype "passive"))
      (node (ref "RN2") (pin "R2B") (pinfunction "2_R2B") (pintype "passive"))
      (node (ref "RN2") (pin "R3B") (pinfunction "3_R3B") (pintype "passive"))
      (node (ref "RN2") (pin "R4B") (pinfunction "4_R4B") (pintype "passive"))
      (node (ref "RN3") (pin "R1B") (pinfunction "1_R1B") (pintype "passive"))
      (node (ref "RN3") (pin "R2B") (pinfunction "2_R2B") (pintype "passive"))
      (node (ref "RN3") (pin "R3B") (pinfunction "3_R3B") (pintype "passive"))
      (node (ref "RN3") (pin "R4B") (pinfunction "4_R4B") (pintype "passive"))
      (node (ref "RN4") (pin "R1B") (pinfunction "1_R1B") (pintype "passive"))
      (node (ref "RN4") (pin "R2B") (pinfunction "2_R2B") (pintype "passive"))
      (node (ref "RN4") (pin "R3B") (pinfunction "3_R3B") (pintype "passive"))
      (node (ref "RN4") (pin "R4B") (pinfunction "4_R4B") (pintype "passive"))
      (node (ref "RN6") (pin "R1A") (pinfunction "1A_R1A") (pintype "passive"))
      (node (ref "RN6") (pin "R2A") (pinfunction "2A_R2A") (pintype "passive"))
      (node (ref "RN6") (pin "R3A") (pinfunction "3A_R3A") (pintype "passive"))
      (node (ref "RN6") (pin "R4A") (pinfunction "4A_R4A") (pintype "passive"))
      (node (ref "RN8") (pin "R1A") (pinfunction "1A_R1A") (pintype "passive"))
      (node (ref "RN8") (pin "R2A") (pinfunction "2A_R2A") (pintype "passive"))
      (node (ref "RN8") (pin "R3A") (pinfunction "3A_R3A") (pintype "passive"))
      (node (ref "RN8") (pin "R4A") (pinfunction "4A_R4A") (pintype "passive"))
      (node (ref "S1") (pin "1") (pinfunction "1_1") (pintype "passive"))
      (node (ref "S1") (pin "2") (pinfunction "2_2") (pintype "passive"))
      (node (ref "S1") (pin "3") (pinfunction "3_3") (pintype "passive"))
      (node (ref "S1") (pin "4") (pinfunction "4_4") (pintype "passive"))
      (node (ref "X1") (pin "2") (pinfunction "KL_2") (pintype "passive"))
      (node (ref "Y1") (pin "2") (pinfunction "2_2") (pintype "passive"))
    )
    (net (code "143") (name "Net-(F1-Pad1)") (class "Default")
      (node (ref "F1") (pin "1") (pinfunction "1_1") (pintype "passive"))
      (node (ref "JP3") (pin "3") (pinfunction "3_3") (pintype "passive"))
    )
    (net (code "144") (name "Net-(F2-Pad2)") (class "Default")
      (node (ref "F2") (pin "2") (pinfunction "2_2") (pintype "passive"))
      (node (ref "JP6") (pin "1") (pinfunction "1_1") (pintype "passive"))
    )
    (net (code "145") (name "Net-(F3-Pad1)") (class "Default")
      (node (ref "F3") (pin "1") (pinfunction "1_1") (pintype "passive"))
      (node (ref "Q1") (pin "S1") (pinfunction "SOURCE_S1") (pintype "bidirectional"))
      (node (ref "Q1") (pin "S2") (pinfunction "SOURCE_S2") (pintype "bidirectional"))
      (node (ref "Q1") (pin "S3") (pinfunction "SOURCE_S3") (pintype "bidirectional"))
    )
    (net (code "146") (name "Net-(IC1-PadCH6)") (class "Default")
      (node (ref "IC1") (pin "CH6") (pinfunction "CH6_CH6") (pintype "input"))
      (node (ref "R15") (pin "2") (pinfunction "2_2") (pintype "passive"))
      (node (ref "R17") (pin "1") (pinfunction "1_1") (pintype "passive"))
    )
    (net (code "147") (name "Net-(IC1-PadCH7)") (class "Default")
      (node (ref "IC1") (pin "CH7") (pinfunction "CH7_CH7") (pintype "input"))
      (node (ref "R13") (pin "2") (pinfunction "2_2") (pintype "passive"))
      (node (ref "R16") (pin "1") (pinfunction "1_1") (pintype "passive"))
    )
    (net (code "148") (name "Net-(IC2-PadCH1)") (class "Default")
      (node (ref "IC2") (pin "CH1") (pinfunction "CH1_CH1") (pintype "input"))
      (node (ref "JP8") (pin "11") (pinfunction "11_11") (pintype "passive"))
    )
    (net (code "149") (name "Net-(IC2-PadCH2)") (class "Default")
      (node (ref "IC2") (pin "CH2") (pinfunction "CH2_CH2") (pintype "input"))
      (node (ref "JP8") (pin "13") (pinfunction "13_13") (pintype "passive"))
    )
    (net (code "150") (name "Net-(IC2-PadCH5)") (class "Default")
      (node (ref "IC2") (pin "CH5") (pinfunction "CH5_CH5") (pintype "input"))
      (node (ref "JP8") (pin "12") (pinfunction "12_12") (pintype "passive"))
    )
    (net (code "151") (name "Net-(IC2-PadCH6)") (class "Default")
      (node (ref "IC2") (pin "CH6") (pinfunction "CH6_CH6") (pintype "input"))
      (node (ref "JP8") (pin "14") (pinfunction "14_14") (pintype "passive"))
    )
    (net (code "152") (name "Net-(IC3-PadCH1)") (class "Default")
      (node (ref "IC3") (pin "CH1") (pinfunction "CH1_CH1") (pintype "input"))
      (node (ref "JP8") (pin "4") (pinfunction "4_4") (pintype "passive"))
    )
    (net (code "153") (name "Net-(IC3-PadCH2)") (class "Default")
      (node (ref "IC3") (pin "CH2") (pinfunction "CH2_CH2") (pintype "input"))
      (node (ref "JP8") (pin "6") (pinfunction "6_6") (pintype "passive"))
    )
    (net (code "154") (name "Net-(IC3-PadCH5)") (class "Default")
      (node (ref "IC3") (pin "CH5") (pinfunction "CH5_CH5") (pintype "input"))
      (node (ref "JP8") (pin "3") (pinfunction "3_3") (pintype "passive"))
    )
    (net (code "155") (name "Net-(IC3-PadCH6)") (class "Default")
      (node (ref "IC3") (pin "CH6") (pinfunction "CH6_CH6") (pintype "input"))
      (node (ref "JP8") (pin "5") (pinfunction "5_5") (pintype "passive"))
    )
    (net (code "156") (name "Net-(IC4-GPA1)") (class "Default")
      (node (ref "IC4") (pin "18") (pinfunction "GPA1_18") (pintype "bidirectional"))
      (node (ref "JP12") (pin "14") (pinfunction "14_14") (pintype "passive"))
    )
    (net (code "157") (name "Net-(IC4-GPA2)") (class "Default")
      (node (ref "IC4") (pin "19") (pinfunction "GPA2_19") (pintype "bidirectional"))
      (node (ref "JP12") (pin "12") (pinfunction "12_12") (pintype "passive"))
    )
    (net (code "158") (name "Net-(IC4-GPA3)") (class "Default")
      (node (ref "IC4") (pin "20") (pinfunction "GPA3_20") (pintype "bidirectional"))
      (node (ref "JP12") (pin "10") (pinfunction "10_10") (pintype "passive"))
    )
    (net (code "159") (name "Net-(IC4-GPA4)") (class "Default")
      (node (ref "IC4") (pin "21") (pinfunction "GPA4_21") (pintype "bidirectional"))
      (node (ref "JP12") (pin "8") (pinfunction "8_8") (pintype "passive"))
    )
    (net (code "160") (name "Net-(IC4-GPA5)") (class "Default")
      (node (ref "IC4") (pin "22") (pinfunction "GPA5_22") (pintype "bidirectional"))
      (node (ref "JP12") (pin "6") (pinfunction "6_6") (pintype "passive"))
    )
    (net (code "161") (name "Net-(IC4-GPA6)") (class "Default")
      (node (ref "IC4") (pin "23") (pinfunction "GPA6_23") (pintype "bidirectional"))
      (node (ref "JP12") (pin "4") (pinfunction "4_4") (pintype "passive"))
    )
    (net (code "162") (name "Net-(IC4-GPB1)") (class "Default")
      (node (ref "IC4") (pin "26") (pinfunction "GPB1_26") (pintype "bidirectional"))
      (node (ref "JP12") (pin "3") (pinfunction "3_3") (pintype "passive"))
    )
    (net (code "163") (name "Net-(IC4-GPB2)") (class "Default")
      (node (ref "IC4") (pin "27") (pinfunction "GPB2_27") (pintype "bidirectional"))
      (node (ref "JP12") (pin "5") (pinfunction "5_5") (pintype "passive"))
    )
    (net (code "164") (name "Net-(IC4-GPB3)") (class "Default")
      (node (ref "IC4") (pin "28") (pinfunction "GPB3_28") (pintype "bidirectional"))
      (node (ref "JP12") (pin "7") (pinfunction "7_7") (pintype "passive"))
    )
    (net (code "165") (name "Net-(IC4-GPB4)") (class "Default")
      (node (ref "IC4") (pin "1") (pinfunction "GPB4_1") (pintype "bidirectional"))
      (node (ref "JP12") (pin "9") (pinfunction "9_9") (pintype "passive"))
    )
    (net (code "166") (name "Net-(IC4-GPB5)") (class "Default")
      (node (ref "IC4") (pin "2") (pinfunction "GPB5_2") (pintype "bidirectional"))
      (node (ref "JP12") (pin "11") (pinfunction "11_11") (pintype "passive"))
    )
    (net (code "167") (name "Net-(IC4-GPB6)") (class "Default")
      (node (ref "IC4") (pin "3") (pinfunction "GPB6_3") (pintype "bidirectional"))
      (node (ref "JP12") (pin "13") (pinfunction "13_13") (pintype "passive"))
    )
    (net (code "168") (name "Net-(IC5-GPA1)") (class "Default")
      (node (ref "IC5") (pin "18") (pinfunction "GPA1_18") (pintype "bidirectional"))
      (node (ref "JP13") (pin "14") (pinfunction "14_14") (pintype "passive"))
    )
    (net (code "169") (name "Net-(IC5-GPA2)") (class "Default")
      (node (ref "IC5") (pin "19") (pinfunction "GPA2_19") (pintype "bidirectional"))
      (node (ref "JP13") (pin "12") (pinfunction "12_12") (pintype "passive"))
    )
    (net (code "170") (name "Net-(IC5-GPA3)") (class "Default")
      (node (ref "IC5") (pin "20") (pinfunction "GPA3_20") (pintype "bidirectional"))
      (node (ref "JP13") (pin "10") (pinfunction "10_10") (pintype "passive"))
    )
    (net (code "171") (name "Net-(IC5-GPA4)") (class "Default")
      (node (ref "IC5") (pin "21") (pinfunction "GPA4_21") (pintype "bidirectional"))
      (node (ref "JP13") (pin "8") (pinfunction "8_8") (pintype "passive"))
    )
    (net (code "172") (name "Net-(IC5-GPA5)") (class "Default")
      (node (ref "IC5") (pin "22") (pinfunction "GPA5_22") (pintype "bidirectional"))
      (node (ref "JP13") (pin "6") (pinfunction "6_6") (pintype "passive"))
    )
    (net (code "173") (name "Net-(IC5-GPA6)") (class "Default")
      (node (ref "IC5") (pin "23") (pinfunction "GPA6_23") (pintype "bidirectional"))
      (node (ref "JP13") (pin "4") (pinfunction "4_4") (pintype "passive"))
    )
    (net (code "174") (name "Net-(IC5-GPB1)") (class "Default")
      (node (ref "IC5") (pin "26") (pinfunction "GPB1_26") (pintype "bidirectional"))
      (node (ref "JP13") (pin "3") (pinfunction "3_3") (pintype "passive"))
    )
    (net (code "175") (name "Net-(IC5-GPB2)") (class "Default")
      (node (ref "IC5") (pin "27") (pinfunction "GPB2_27") (pintype "bidirectional"))
      (node (ref "JP13") (pin "5") (pinfunction "5_5") (pintype "passive"))
    )
    (net (code "176") (name "Net-(IC5-GPB3)") (class "Default")
      (node (ref "IC5") (pin "28") (pinfunction "GPB3_28") (pintype "bidirectional"))
      (node (ref "JP13") (pin "7") (pinfunction "7_7") (pintype "passive"))
    )
    (net (code "177") (name "Net-(IC5-GPB4)") (class "Default")
      (node (ref "IC5") (pin "1") (pinfunction "GPB4_1") (pintype "bidirectional"))
      (node (ref "JP13") (pin "9") (pinfunction "9_9") (pintype "passive"))
    )
    (net (code "178") (name "Net-(IC5-GPB5)") (class "Default")
      (node (ref "IC5") (pin "2") (pinfunction "GPB5_2") (pintype "bidirectional"))
      (node (ref "JP13") (pin "11") (pinfunction "11_11") (pintype "passive"))
    )
    (net (code "179") (name "Net-(IC5-GPB6)") (class "Default")
      (node (ref "IC5") (pin "3") (pinfunction "GPB6_3") (pintype "bidirectional"))
      (node (ref "JP13") (pin "13") (pinfunction "13_13") (pintype "passive"))
    )
    (net (code "180") (name "Net-(IC8-PB6(XTAL1{slash}TOSC1))") (class "Default")
      (node (ref "IC8") (pin "5") (pinfunction "PB6(XTAL1/TOSC1)_5") (pintype "bidirectional"))
      (node (ref "Y1") (pin "1") (pinfunction "1_1") (pintype "passive"))
    )
    (net (code "181") (name "Net-(IC8-PB7(XTAL2{slash}TOSC2))") (class "Default")
      (node (ref "IC8") (pin "6") (pinfunction "PB7(XTAL2/TOSC2)_6") (pintype "bidirectional"))
      (node (ref "Y1") (pin "3") (pinfunction "3_3") (pintype "passive"))
    )
    (net (code "182") (name "Net-(IC12-IP+)") (class "Default")
      (node (ref "IC12") (pin "5") (pinfunction "IP+_5") (pintype "bidirectional"))
      (node (ref "X6") (pin "2") (pinfunction "KL_2") (pintype "passive"))
    )
    (net (code "183") (name "Net-(IC12-IP-)") (class "Default")
      (node (ref "IC12") (pin "6") (pinfunction "IP-_6") (pintype "bidirectional"))
      (node (ref "X6") (pin "1") (pinfunction "KL_1") (pintype "passive"))
    )
    (net (code "184") (name "Net-(IC12-VOUT)") (class "Default")
      (node (ref "IC12") (pin "3") (pinfunction "VOUT_3") (pintype "bidirectional"))
      (node (ref "R10") (pin "1") (pinfunction "1_1") (pintype "passive"))
    )
    (net (code "185") (name "Net-(IC13-IP+)") (class "Default")
      (node (ref "IC13") (pin "5") (pinfunction "IP+_5") (pintype "bidirectional"))
      (node (ref "X7") (pin "2") (pinfunction "KL_2") (pintype "passive"))
    )
    (net (code "186") (name "Net-(IC13-IP-)") (class "Default")
      (node (ref "IC13") (pin "6") (pinfunction "IP-_6") (pintype "bidirectional"))
      (node (ref "X7") (pin "1") (pinfunction "KL_1") (pintype "passive"))
    )
    (net (code "187") (name "Net-(IC13-VOUT)") (class "Default")
      (node (ref "IC13") (pin "3") (pinfunction "VOUT_3") (pintype "bidirectional"))
      (node (ref "R11") (pin "1") (pinfunction "1_1") (pintype "passive"))
    )
    (net (code "188") (name "Net-(LEAK1-Pad1)") (class "Default")
      (node (ref "LEAK1") (pin "1") (pinfunction "1_1") (pintype "bidirectional"))
      (node (ref "R12") (pin "2") (pinfunction "2_2") (pintype "passive"))
    )
    (net (code "189") (name "Net-(LEAK2-Pad1)") (class "Default")
      (node (ref "LEAK2") (pin "1") (pinfunction "1_1") (pintype "bidirectional"))
      (node (ref "R19") (pin "2") (pinfunction "2_2") (pintype "passive"))
    )
    (net (code "190") (name "Net-(LEAK3-Pad1)") (class "Default")
      (node (ref "LEAK3") (pin "1") (pinfunction "1_1") (pintype "bidirectional"))
      (node (ref "R21") (pin "2") (pinfunction "2_2") (pintype "passive"))
    )
    (net (code "191") (name "Net-(LEAK4-Pad1)") (class "Default")
      (node (ref "LEAK4") (pin "1") (pinfunction "1_1") (pintype "bidirectional"))
      (node (ref "R23") (pin "2") (pinfunction "2_2") (pintype "passive"))
    )
    (net (code "192") (name "Net-(LEAK5-Pad1)") (class "Default")
      (node (ref "LEAK5") (pin "1") (pinfunction "1_1") (pintype "bidirectional"))
      (node (ref "R14") (pin "2") (pinfunction "2_2") (pintype "passive"))
    )
    (net (code "193") (name "Net-(LEAK6-Pad1)") (class "Default")
      (node (ref "LEAK6") (pin "1") (pinfunction "1_1") (pintype "bidirectional"))
      (node (ref "R20") (pin "2") (pinfunction "2_2") (pintype "passive"))
    )
    (net (code "194") (name "Net-(LEAK7-Pad1)") (class "Default")
      (node (ref "LEAK7") (pin "1") (pinfunction "1_1") (pintype "bidirectional"))
      (node (ref "R22") (pin "2") (pinfunction "2_2") (pintype "passive"))
    )
    (net (code "195") (name "Net-(LEAK8-Pad1)") (class "Default")
      (node (ref "LEAK8") (pin "1") (pinfunction "1_1") (pintype "bidirectional"))
      (node (ref "R24") (pin "2") (pinfunction "2_2") (pintype "passive"))
    )
    (net (code "196") (name "Net-(LED1-PadA)") (class "Default")
      (node (ref "LED1") (pin "A") (pinfunction "A_A") (pintype "passive"))
      (node (ref "R26") (pin "2") (pinfunction "2_2") (pintype "passive"))
    )
    (net (code "197") (name "Net-(LED2-PadA)") (class "Default")
      (node (ref "LED2") (pin "A") (pinfunction "A_A") (pintype "passive"))
      (node (ref "R27") (pin "1") (pinfunction "1_1") (pintype "passive"))
    )
    (net (code "198") (name "Net-(LED3-PadA)") (class "Default")
      (node (ref "LED3") (pin "A") (pinfunction "A_A") (pintype "passive"))
      (node (ref "R28") (pin "1") (pinfunction "1_1") (pintype "passive"))
    )
    (net (code "199") (name "Net-(LED4-PadA)") (class "Default")
      (node (ref "LED4") (pin "A") (pinfunction "A_A") (pintype "passive"))
      (node (ref "R29") (pin "1") (pinfunction "1_1") (pintype "passive"))
    )
    (net (code "200") (name "Net-(Q1-GATE)") (class "Default")
      (node (ref "Q1") (pin "G") (pinfunction "GATE_G") (pintype "bidirectional"))
      (node (ref "R1") (pin "1") (pinfunction "1_1") (pintype "passive"))
    )
    (net (code "201") (name "Net-(Q2-GATE)") (class "Default")
      (node (ref "Q2") (pin "G") (pinfunction "GATE_G") (pintype "bidirectional"))
      (node (ref "R2") (pin "2") (pinfunction "2_2") (pintype "passive"))
      (node (ref "R3") (pin "2") (pinfunction "2_2") (pintype "passive"))
    )
    (net (code "202") (name "Net-(Q3-GATE)") (class "Default")
      (node (ref "Q3") (pin "G") (pinfunction "GATE_G") (pintype "bidirectional"))
      (node (ref "R4") (pin "2") (pinfunction "2_2") (pintype "passive"))
      (node (ref "R5") (pin "2") (pinfunction "2_2") (pintype "passive"))
    )
    (net (code "203") (name "Net-(Q4-GATE)") (class "Default")
      (node (ref "Q4") (pin "G") (pinfunction "GATE_G") (pintype "bidirectional"))
      (node (ref "R6") (pin "2") (pinfunction "2_2") (pintype "passive"))
      (node (ref "R7") (pin "2") (pinfunction "2_2") (pintype "passive"))
    )
    (net (code "204") (name "Net-(Q5-GATE)") (class "Default")
      (node (ref "Q5") (pin "G") (pinfunction "GATE_G") (pintype "bidirectional"))
      (node (ref "R8") (pin "2") (pinfunction "2_2") (pintype "passive"))
      (node (ref "R9") (pin "2") (pinfunction "2_2") (pintype "passive"))
    )
    (net (code "205") (name "Net-(RN5-1A)") (class "Default")
      (node (ref "R23") (pin "1") (pinfunction "1_1") (pintype "passive"))
      (node (ref "RN5") (pin "R1A") (pinfunction "1A_R1A") (pintype "passive"))
      (node (ref "T7") (pin "B") (pinfunction "B_B") (pintype "passive"))
    )
    (net (code "206") (name "Net-(RN5-2A)") (class "Default")
      (node (ref "R21") (pin "1") (pinfunction "1_1") (pintype "passive"))
      (node (ref "RN5") (pin "R2A") (pinfunction "2A_R2A") (pintype "passive"))
      (node (ref "T5") (pin "B") (pinfunction "B_B") (pintype "passive"))
    )
    (net (code "207") (name "Net-(RN5-3A)") (class "Default")
      (node (ref "R19") (pin "1") (pinfunction "1_1") (pintype "passive"))
      (node (ref "RN5") (pin "R3A") (pinfunction "3A_R3A") (pintype "passive"))
      (node (ref "T3") (pin "B") (pinfunction "B_B") (pintype "passive"))
    )
    (net (code "208") (name "Net-(RN5-4A)") (class "Default")
      (node (ref "R12") (pin "1") (pinfunction "1_1") (pintype "passive"))
      (node (ref "RN5") (pin "R4A") (pinfunction "4A_R4A") (pintype "passive"))
      (node (ref "T1") (pin "B") (pinfunction "B_B") (pintype "passive"))
    )
    (net (code "209") (name "Net-(RN7-1A)") (class "Default")
      (node (ref "R24") (pin "1") (pinfunction "1_1") (pintype "passive"))
      (node (ref "RN7") (pin "R1A") (pinfunction "1A_R1A") (pintype "passive"))
      (node (ref "T8") (pin "B") (pinfunction "B_B") (pintype "passive"))
    )
    (net (code "210") (name "Net-(RN7-2A)") (class "Default")
      (node (ref "R22") (pin "1") (pinfunction "1_1") (pintype "passive"))
      (node (ref "RN7") (pin "R2A") (pinfunction "2A_R2A") (pintype "passive"))
      (node (ref "T6") (pin "B") (pinfunction "B_B") (pintype "passive"))
    )
    (net (code "211") (name "Net-(RN7-3A)") (class "Default")
      (node (ref "R20") (pin "1") (pinfunction "1_1") (pintype "passive"))
      (node (ref "RN7") (pin "R3A") (pinfunction "3A_R3A") (pintype "passive"))
      (node (ref "T4") (pin "B") (pinfunction "B_B") (pintype "passive"))
    )
    (net (code "212") (name "Net-(RN7-4A)") (class "Default")
      (node (ref "R14") (pin "1") (pinfunction "1_1") (pintype "passive"))
      (node (ref "RN7") (pin "R4A") (pinfunction "4A_R4A") (pintype "passive"))
      (node (ref "T2") (pin "B") (pinfunction "B_B") (pintype "passive"))
    )
    (net (code "213") (name "Net-(RN9-1A)") (class "Default")
      (node (ref "JP10") (pin "1") (pinfunction "1_1") (pintype "passive"))
      (node (ref "RN9") (pin "R1A") (pinfunction "1A_R1A") (pintype "passive"))
    )
    (net (code "214") (name "Net-(RN9-2A)") (class "Default")
      (node (ref "JP10") (pin "3") (pinfunction "3_3") (pintype "passive"))
      (node (ref "RN9") (pin "R2A") (pinfunction "2A_R2A") (pintype "passive"))
    )
    (net (code "215") (name "Net-(RN9-3A)") (class "Default")
      (node (ref "JP10") (pin "5") (pinfunction "5_5") (pintype "passive"))
      (node (ref "RN9") (pin "R3A") (pinfunction "3A_R3A") (pintype "passive"))
    )
    (net (code "216") (name "Net-(RN9-4A)") (class "Default")
      (node (ref "JP10") (pin "7") (pinfunction "7_7") (pintype "passive"))
      (node (ref "RN9") (pin "R4A") (pinfunction "4A_R4A") (pintype "passive"))
    )
    (net (code "217") (name "Net-(RN10-1A)") (class "Default")
      (node (ref "JP10") (pin "9") (pinfunction "9_9") (pintype "passive"))
      (node (ref "RN10") (pin "R1A") (pinfunction "1A_R1A") (pintype "passive"))
    )
    (net (code "218") (name "Net-(RN10-2A)") (class "Default")
      (node (ref "JP10") (pin "11") (pinfunction "11_11") (pintype "passive"))
      (node (ref "RN10") (pin "R2A") (pinfunction "2A_R2A") (pintype "passive"))
    )
    (net (code "219") (name "Net-(RN10-3A)") (class "Default")
      (node (ref "JP10") (pin "13") (pinfunction "13_13") (pintype "passive"))
      (node (ref "RN10") (pin "R3A") (pinfunction "3A_R3A") (pintype "passive"))
    )
    (net (code "220") (name "Net-(RN10-4A)") (class "Default")
      (node (ref "JP10") (pin "15") (pinfunction "15_15") (pintype "passive"))
      (node (ref "RN10") (pin "R4A") (pinfunction "4A_R4A") (pintype "passive"))
    )
    (net (code "221") (name "Net-(RN11-1A)") (class "Default")
      (node (ref "JP11") (pin "1") (pinfunction "1_1") (pintype "passive"))
      (node (ref "RN11") (pin "R1A") (pinfunction "1A_R1A") (pintype "passive"))
    )
    (net (code "222") (name "Net-(RN11-2A)") (class "Default")
      (node (ref "JP11") (pin "3") (pinfunction "3_3") (pintype "passive"))
      (node (ref "RN11") (pin "R2A") (pinfunction "2A_R2A") (pintype "passive"))
    )
    (net (code "223") (name "Net-(RN11-3A)") (class "Default")
      (node (ref "JP11") (pin "5") (pinfunction "5_5") (pintype "passive"))
      (node (ref "RN11") (pin "R3A") (pinfunction "3A_R3A") (pintype "passive"))
    )
    (net (code "224") (name "Net-(RN11-4A)") (class "Default")
      (node (ref "JP11") (pin "7") (pinfunction "7_7") (pintype "passive"))
      (node (ref "RN11") (pin "R4A") (pinfunction "4A_R4A") (pintype "passive"))
    )
    (net (code "225") (name "Net-(RN12-1A)") (class "Default")
      (node (ref "JP11") (pin "9") (pinfunction "9_9") (pintype "passive"))
      (node (ref "RN12") (pin "R1A") (pinfunction "1A_R1A") (pintype "passive"))
    )
    (net (code "226") (name "Net-(RN12-2A)") (class "Default")
      (node (ref "JP11") (pin "11") (pinfunction "11_11") (pintype "passive"))
      (node (ref "RN12") (pin "R2A") (pinfunction "2A_R2A") (pintype "passive"))
    )
    (net (code "227") (name "Net-(RN12-3A)") (class "Default")
      (node (ref "JP11") (pin "13") (pinfunction "13_13") (pintype "passive"))
      (node (ref "RN12") (pin "R3A") (pinfunction "3A_R3A") (pintype "passive"))
    )
    (net (code "228") (name "Net-(RN12-4A)") (class "Default")
      (node (ref "JP11") (pin "15") (pinfunction "15_15") (pintype "passive"))
      (node (ref "RN12") (pin "R4A") (pinfunction "4A_R4A") (pintype "passive"))
    )
    (net (code "229") (name "Net-(RN13-1A)") (class "Default")
      (node (ref "JP10") (pin "8") (pinfunction "8_8") (pintype "passive"))
      (node (ref "RN13") (pin "R1A") (pinfunction "1A_R1A") (pintype "passive"))
    )
    (net (code "230") (name "Net-(RN13-2A)") (class "Default")
      (node (ref "JP10") (pin "6") (pinfunction "6_6") (pintype "passive"))
      (node (ref "RN13") (pin "R2A") (pinfunction "2A_R2A") (pintype "passive"))
    )
    (net (code "231") (name "Net-(RN13-3A)") (class "Default")
      (node (ref "JP10") (pin "4") (pinfunction "4_4") (pintype "passive"))
      (node (ref "RN13") (pin "R3A") (pinfunction "3A_R3A") (pintype "passive"))
    )
    (net (code "232") (name "Net-(RN13-4A)") (class "Default")
      (node (ref "JP10") (pin "2") (pinfunction "2_2") (pintype "passive"))
      (node (ref "RN13") (pin "R4A") (pinfunction "4A_R4A") (pintype "passive"))
    )
    (net (code "233") (name "Net-(RN14-1A)") (class "Default")
      (node (ref "JP10") (pin "16") (pinfunction "16_16") (pintype "passive"))
      (node (ref "RN14") (pin "R1A") (pinfunction "1A_R1A") (pintype "passive"))
    )
    (net (code "234") (name "Net-(RN14-2A)") (class "Default")
      (node (ref "JP10") (pin "14") (pinfunction "14_14") (pintype "passive"))
      (node (ref "RN14") (pin "R2A") (pinfunction "2A_R2A") (pintype "passive"))
    )
    (net (code "235") (name "Net-(RN14-3A)") (class "Default")
      (node (ref "JP10") (pin "12") (pinfunction "12_12") (pintype "passive"))
      (node (ref "RN14") (pin "R3A") (pinfunction "3A_R3A") (pintype "passive"))
    )
    (net (code "236") (name "Net-(RN14-4A)") (class "Default")
      (node (ref "JP10") (pin "10") (pinfunction "10_10") (pintype "passive"))
      (node (ref "RN14") (pin "R4A") (pinfunction "4A_R4A") (pintype "passive"))
    )
    (net (code "237") (name "Net-(RN15-1A)") (class "Default")
      (node (ref "JP11") (pin "8") (pinfunction "8_8") (pintype "passive"))
      (node (ref "RN15") (pin "R1A") (pinfunction "1A_R1A") (pintype "passive"))
    )
    (net (code "238") (name "Net-(RN15-2A)") (class "Default")
      (node (ref "JP11") (pin "6") (pinfunction "6_6") (pintype "passive"))
      (node (ref "RN15") (pin "R2A") (pinfunction "2A_R2A") (pintype "passive"))
    )
    (net (code "239") (name "Net-(RN15-3A)") (class "Default")
      (node (ref "JP11") (pin "4") (pinfunction "4_4") (pintype "passive"))
      (node (ref "RN15") (pin "R3A") (pinfunction "3A_R3A") (pintype "passive"))
    )
    (net (code "240") (name "Net-(RN15-4A)") (class "Default")
      (node (ref "JP11") (pin "2") (pinfunction "2_2") (pintype "passive"))
      (node (ref "RN15") (pin "R4A") (pinfunction "4A_R4A") (pintype "passive"))
    )
    (net (code "241") (name "Net-(RN16-1A)") (class "Default")
      (node (ref "JP11") (pin "16") (pinfunction "16_16") (pintype "passive"))
      (node (ref "RN16") (pin "R1A") (pinfunction "1A_R1A") (pintype "passive"))
    )
    (net (code "242") (name "Net-(RN16-2A)") (class "Default")
      (node (ref "JP11") (pin "14") (pinfunction "14_14") (pintype "passive"))
      (node (ref "RN16") (pin "R2A") (pinfunction "2A_R2A") (pintype "passive"))
    )
    (net (code "243") (name "Net-(RN16-3A)") (class "Default")
      (node (ref "JP11") (pin "12") (pinfunction "12_12") (pintype "passive"))
      (node (ref "RN16") (pin "R3A") (pinfunction "3A_R3A") (pintype "passive"))
    )
    (net (code "244") (name "Net-(RN16-4A)") (class "Default")
      (node (ref "JP11") (pin "10") (pinfunction "10_10") (pintype "passive"))
      (node (ref "RN16") (pin "R4A") (pinfunction "4A_R4A") (pintype "passive"))
    )
    (net (code "245") (name "Net-(X2B-KL)") (class "Default")
      (node (ref "Q2") (pin "D0") (pinfunction "DRAIN_D0") (pintype "bidirectional"))
      (node (ref "Q2") (pin "D1") (pinfunction "DRAIN_D1") (pintype "bidirectional"))
      (node (ref "Q2") (pin "D2") (pinfunction "DRAIN_D2") (pintype "bidirectional"))
      (node (ref "Q2") (pin "D3") (pinfunction "DRAIN_D3") (pintype "bidirectional"))
      (node (ref "Q2") (pin "D4") (pinfunction "DRAIN_D4") (pintype "bidirectional"))
      (node (ref "X2") (pin "2") (pinfunction "KL_2") (pintype "passive"))
    )
    (net (code "246") (name "Net-(X3B-KL)") (class "Default")
      (node (ref "Q3") (pin "D0") (pinfunction "DRAIN_D0") (pintype "bidirectional"))
      (node (ref "Q3") (pin "D1") (pinfunction "DRAIN_D1") (pintype "bidirectional"))
      (node (ref "Q3") (pin "D2") (pinfunction "DRAIN_D2") (pintype "bidirectional"))
      (node (ref "Q3") (pin "D3") (pinfunction "DRAIN_D3") (pintype "bidirectional"))
      (node (ref "Q3") (pin "D4") (pinfunction "DRAIN_D4") (pintype "bidirectional"))
      (node (ref "X3") (pin "2") (pinfunction "KL_2") (pintype "passive"))
    )
    (net (code "247") (name "Net-(X4B-KL)") (class "Default")
      (node (ref "Q4") (pin "D0") (pinfunction "DRAIN_D0") (pintype "bidirectional"))
      (node (ref "Q4") (pin "D1") (pinfunction "DRAIN_D1") (pintype "bidirectional"))
      (node (ref "Q4") (pin "D2") (pinfunction "DRAIN_D2") (pintype "bidirectional"))
      (node (ref "Q4") (pin "D3") (pinfunction "DRAIN_D3") (pintype "bidirectional"))
      (node (ref "Q4") (pin "D4") (pinfunction "DRAIN_D4") (pintype "bidirectional"))
      (node (ref "X4") (pin "2") (pinfunction "KL_2") (pintype "passive"))
    )
    (net (code "248") (name "Net-(X5B-KL)") (class "Default")
      (node (ref "Q5") (pin "D0") (pinfunction "DRAIN_D0") (pintype "bidirectional"))
      (node (ref "Q5") (pin "D1") (pinfunction "DRAIN_D1") (pintype "bidirectional"))
      (node (ref "Q5") (pin "D2") (pinfunction "DRAIN_D2") (pintype "bidirectional"))
      (node (ref "Q5") (pin "D3") (pinfunction "DRAIN_D3") (pintype "bidirectional"))
      (node (ref "Q5") (pin "D4") (pinfunction "DRAIN_D4") (pintype "bidirectional"))
      (node (ref "X5") (pin "2") (pinfunction "KL_2") (pintype "passive"))
    )
    (net (code "249") (name "RXI") (class "Default")
      (node (ref "IC8") (pin "26") (pinfunction "PD0(RXD)_26") (pintype "bidirectional"))
      (node (ref "JP16") (pin "10") (pinfunction "10_10") (pintype "passive"))
    )
    (net (code "250") (name "TXO") (class "Default")
      (node (ref "IC8") (pin "27") (pinfunction "PD1(TXD)_27") (pintype "bidirectional"))
      (node (ref "JP16") (pin "8") (pinfunction "8_8") (pintype "passive"))
    )
    (net (code "251") (name "VCC") (class "Default")
      (node (ref "JP9") (pin "1") (pinfunction "1_1") (pintype "passive"))
      (node (ref "R16") (pin "2") (pinfunction "2_2") (pintype "passive"))
    )
    (net (code "252") (name "unconnected-(IC4-INTA-Pad16)") (class "Default")
      (node (ref "IC4") (pin "16") (pinfunction "INTA_16") (pintype "output"))
    )
    (net (code "253") (name "unconnected-(IC4-INTB-Pad15)") (class "Default")
      (node (ref "IC4") (pin "15") (pinfunction "INTB_15") (pintype "output"))
    )
    (net (code "254") (name "unconnected-(IC5-INTA-Pad16)") (class "Default")
      (node (ref "IC5") (pin "16") (pinfunction "INTA_16") (pintype "output"))
    )
    (net (code "255") (name "unconnected-(IC5-INTB-Pad15)") (class "Default")
      (node (ref "IC5") (pin "15") (pinfunction "INTB_15") (pintype "output"))
    )
    (net (code "256") (name "unconnected-(IC8-AREF-Pad17)") (class "Default")
      (node (ref "IC8") (pin "17") (pinfunction "AREF_17") (pintype "bidirectional"))
    )
    (net (code "257") (name "unconnected-(IC9-INTA-Pad16)") (class "Default")
      (node (ref "IC9") (pin "16") (pinfunction "INTA_16") (pintype "output"))
    )
    (net (code "258") (name "unconnected-(IC9-INTB-Pad15)") (class "Default")
      (node (ref "IC9") (pin "15") (pinfunction "INTB_15") (pintype "output"))
    )
    (net (code "259") (name "unconnected-(JMP2-Pad3)") (class "Default")
      (node (ref "JMP2") (pin "3") (pinfunction "3_3") (pintype "passive"))
    )
    (net (code "260") (name "unconnected-(JP15-Pad2)") (class "Default")
      (node (ref "JP15") (pin "2") (pinfunction "2_2") (pintype "passive"))
    )
    (net (code "261") (name "unconnected-(RN3-4A-PadR4A)") (class "Default")
      (node (ref "RN3") (pin "R4A") (pinfunction "4A_R4A") (pintype "passive"))
    )
    (net (code "262") (name "unconnected-(RN4-4A-PadR4A)") (class "Default")
      (node (ref "RN4") (pin "R4A") (pinfunction "4A_R4A") (pintype "passive"))
    )
  )
)
